# rekick2015-Prototyp-Sperrwandler.net
KiCad netlist of a schematic drawn in EAGLE
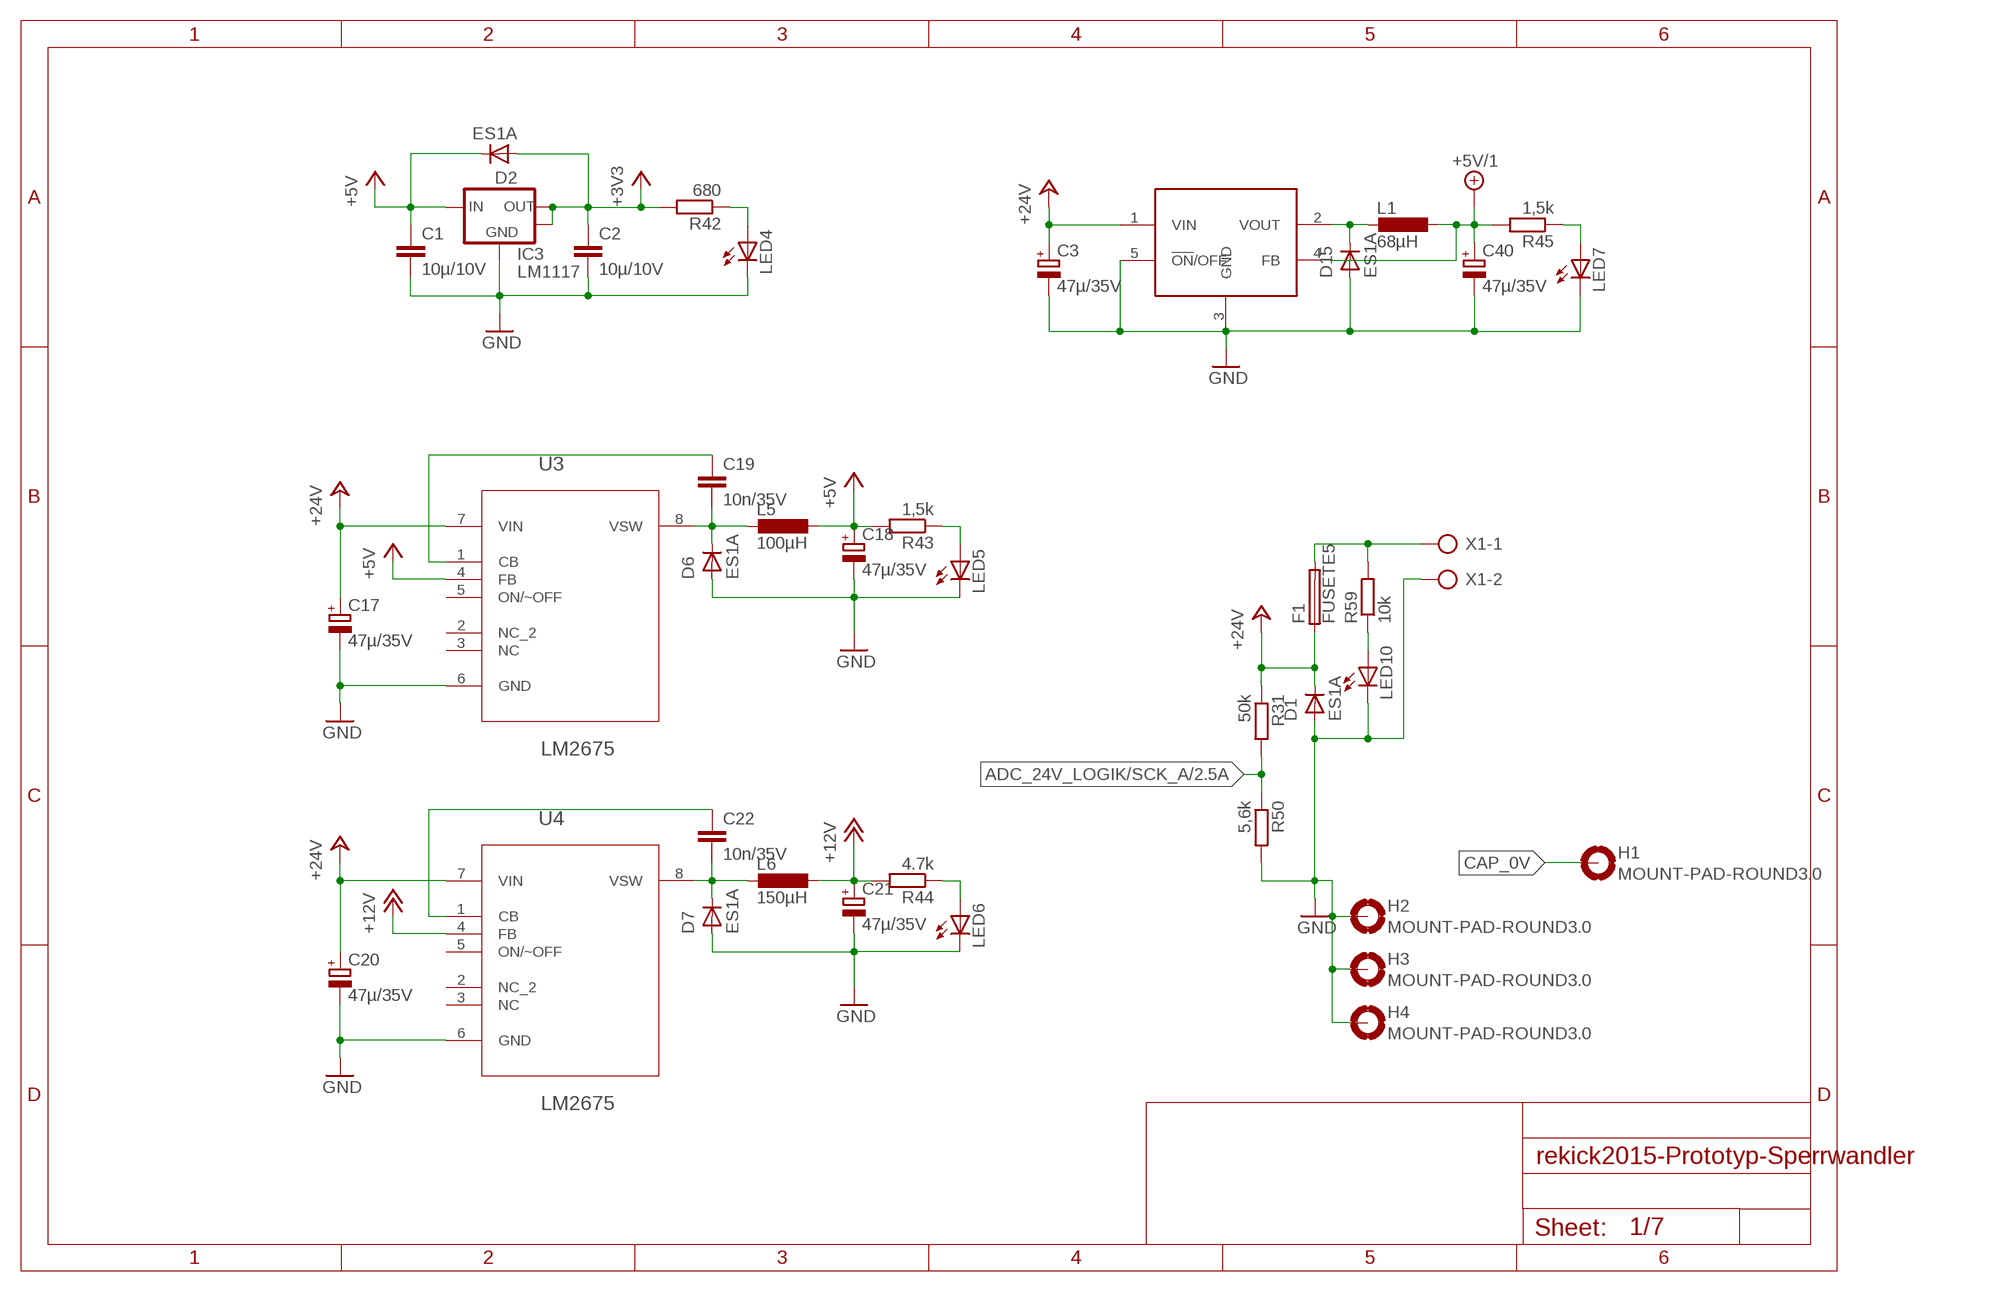
[diagram p0: schematic, sheet 1]
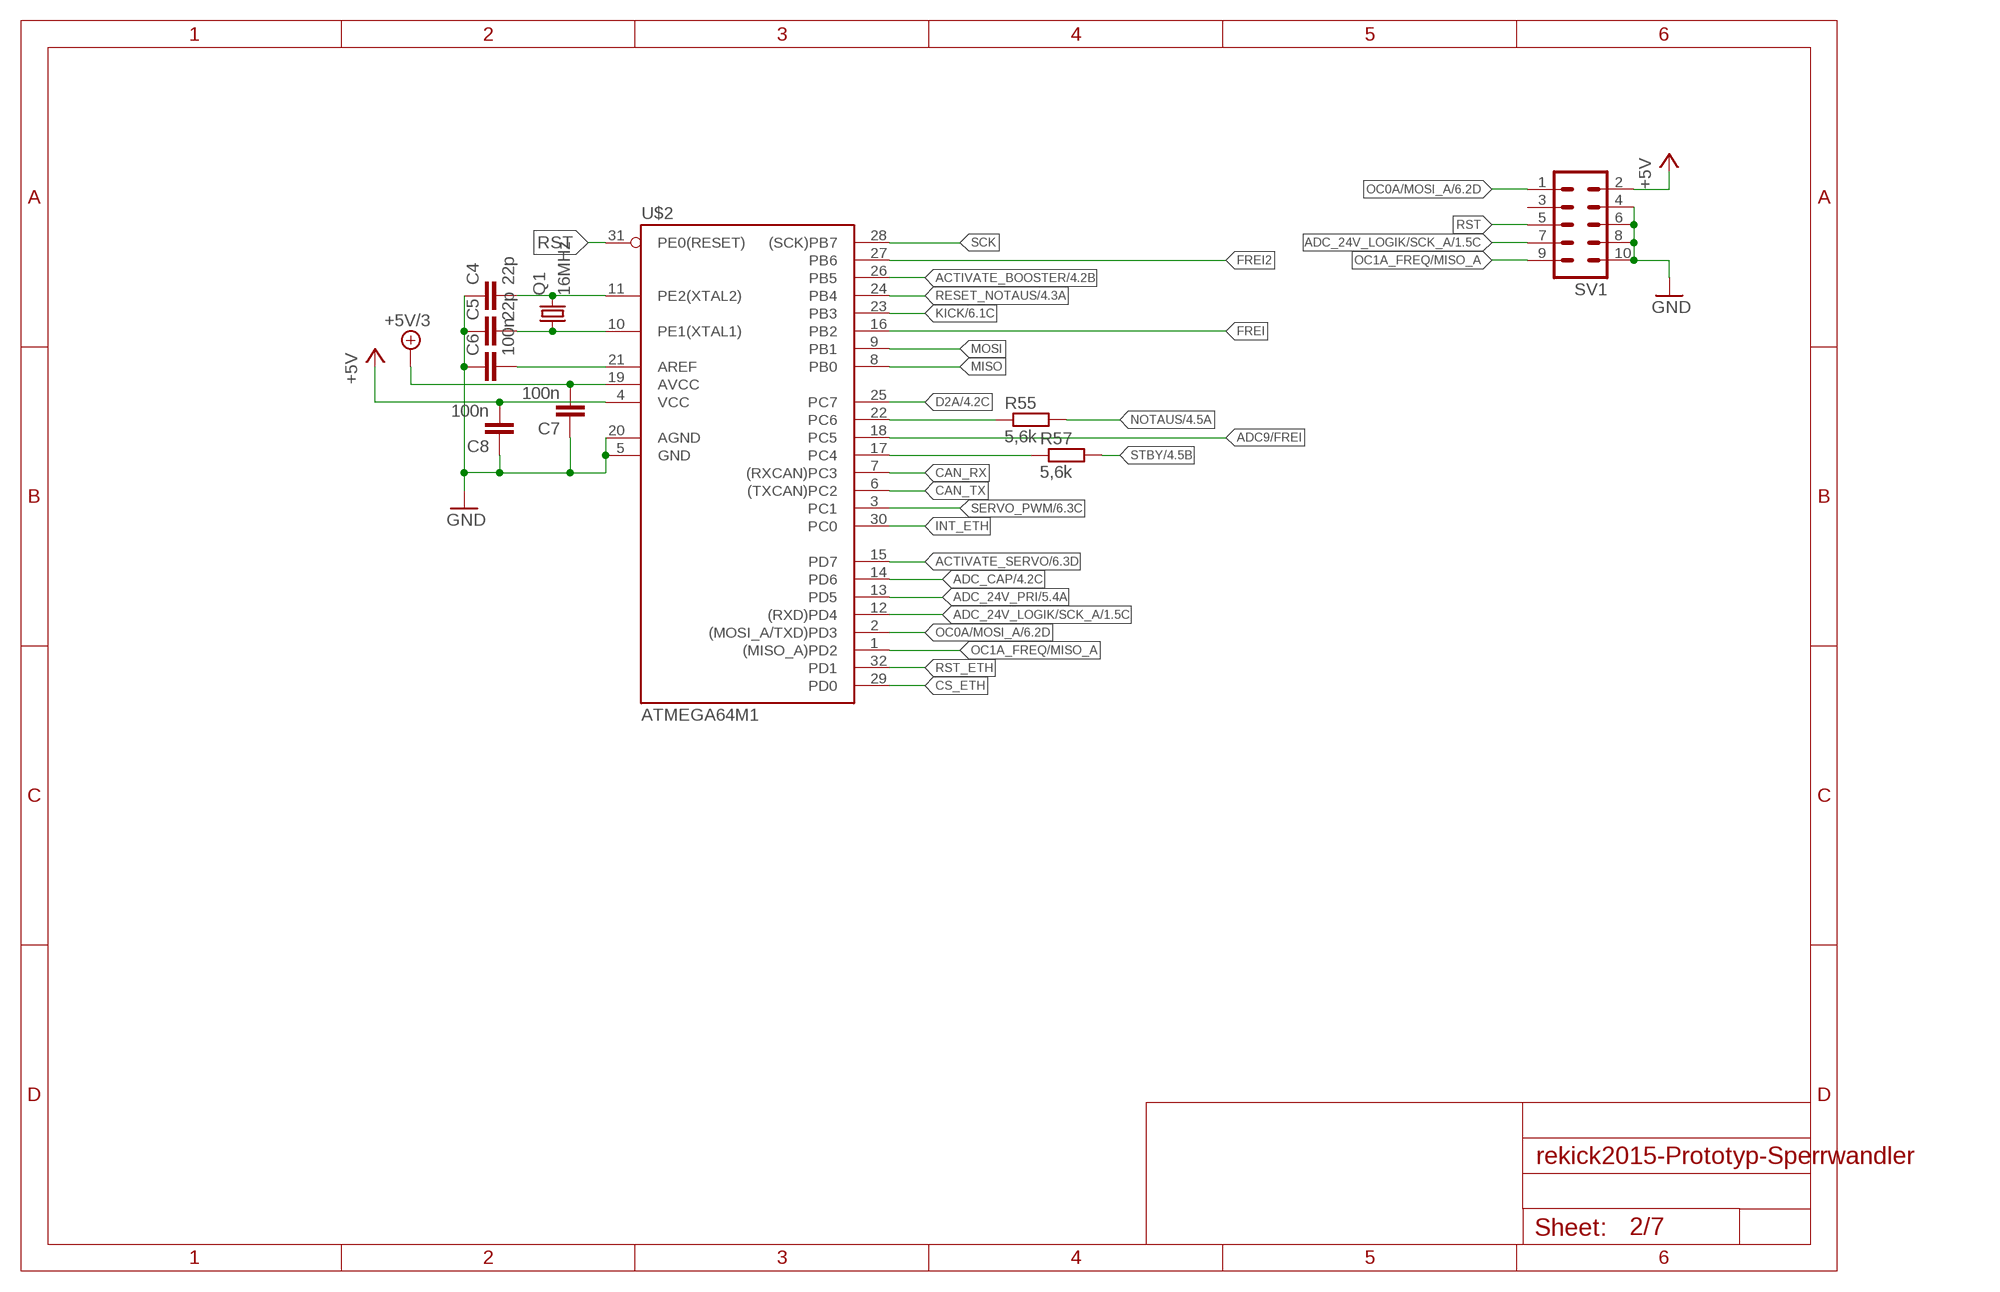
[diagram p1: schematic, sheet 2]
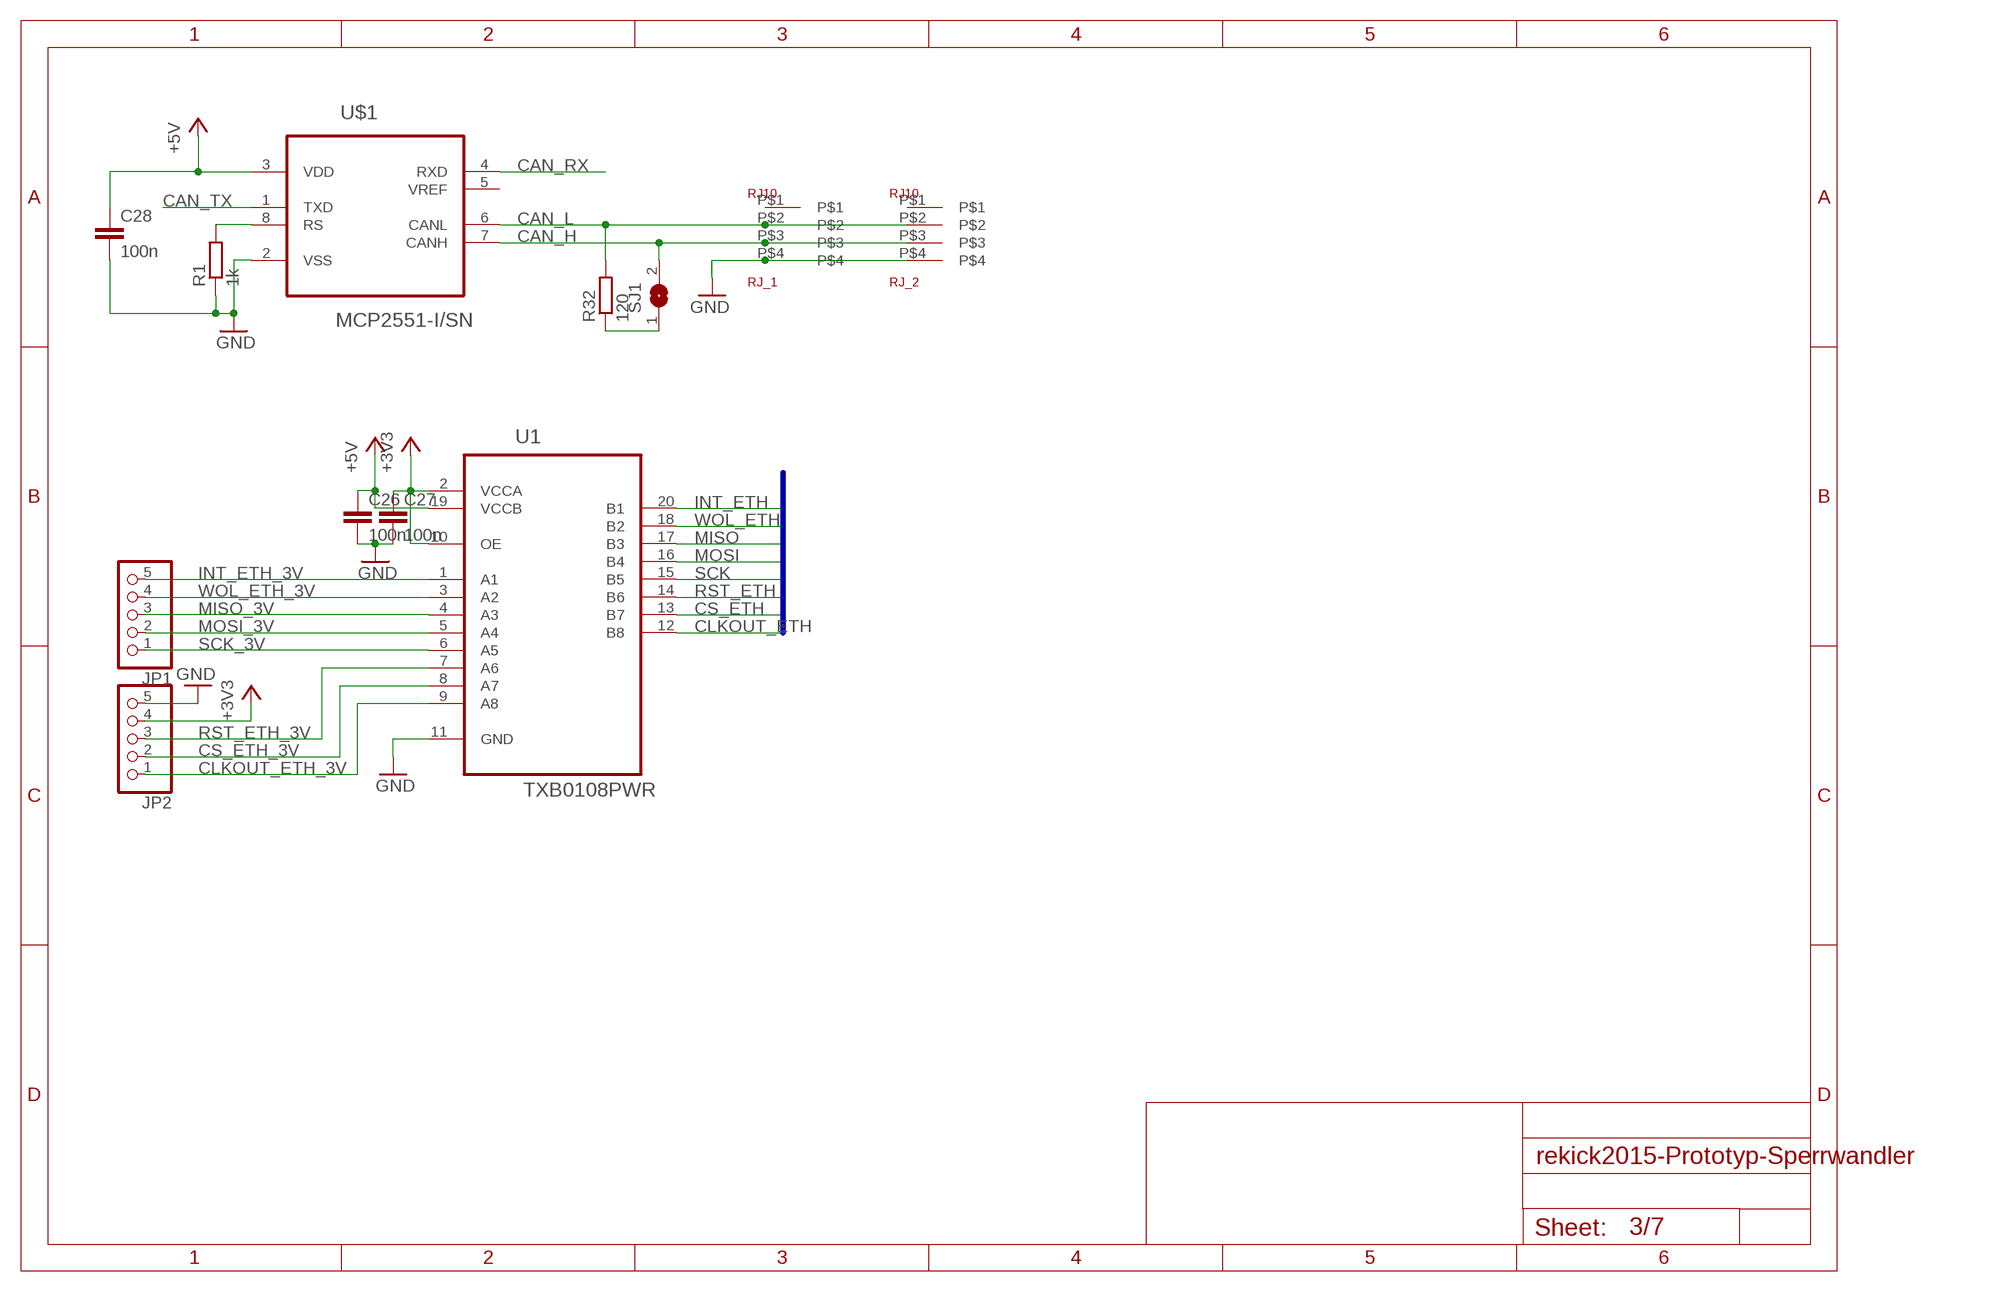
[diagram p2: schematic, sheet 3]
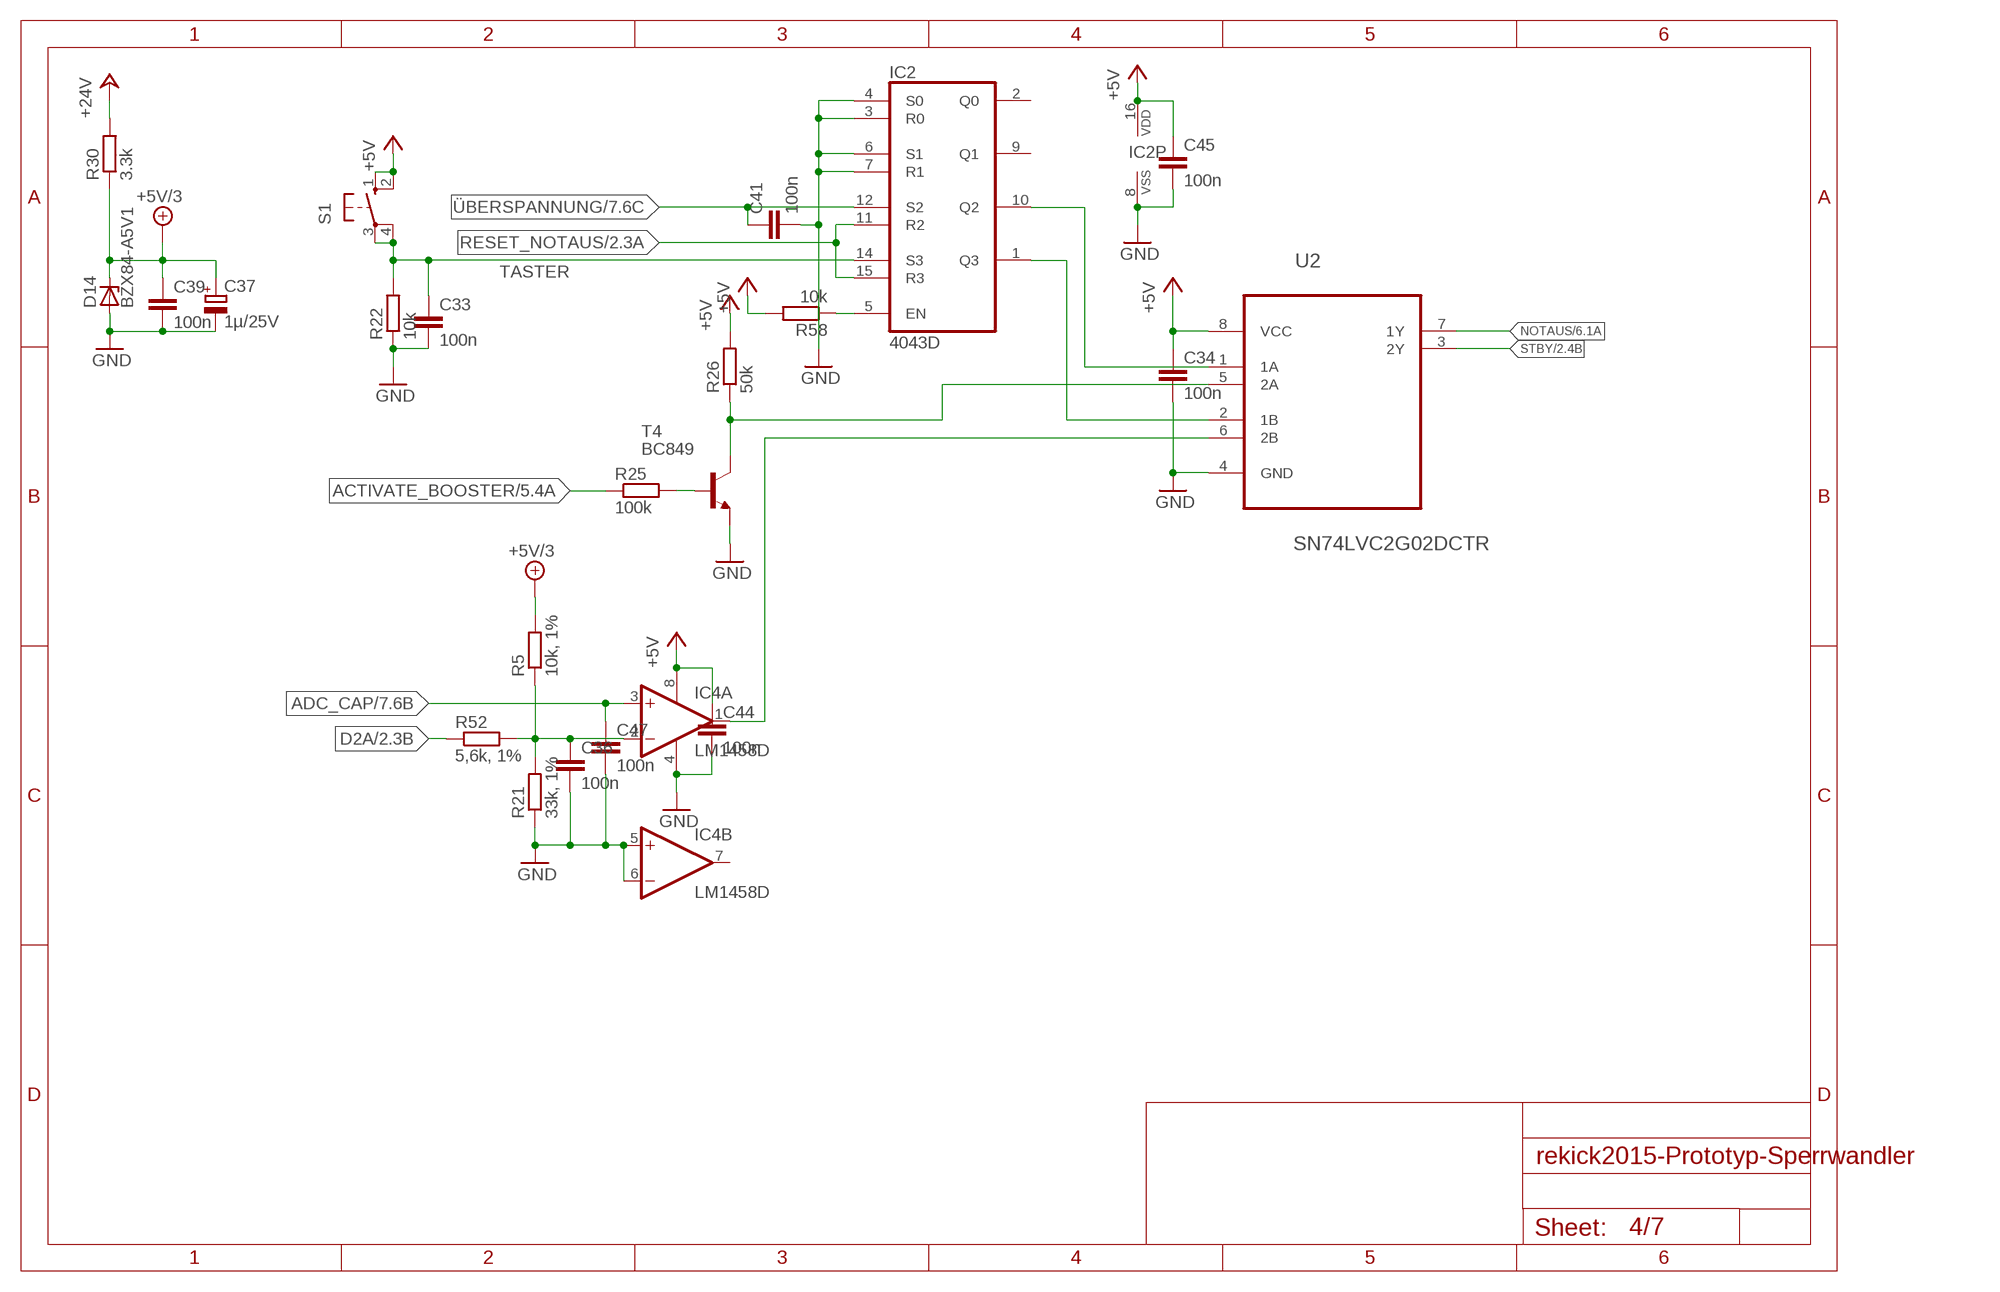
[diagram p3: schematic, sheet 4]
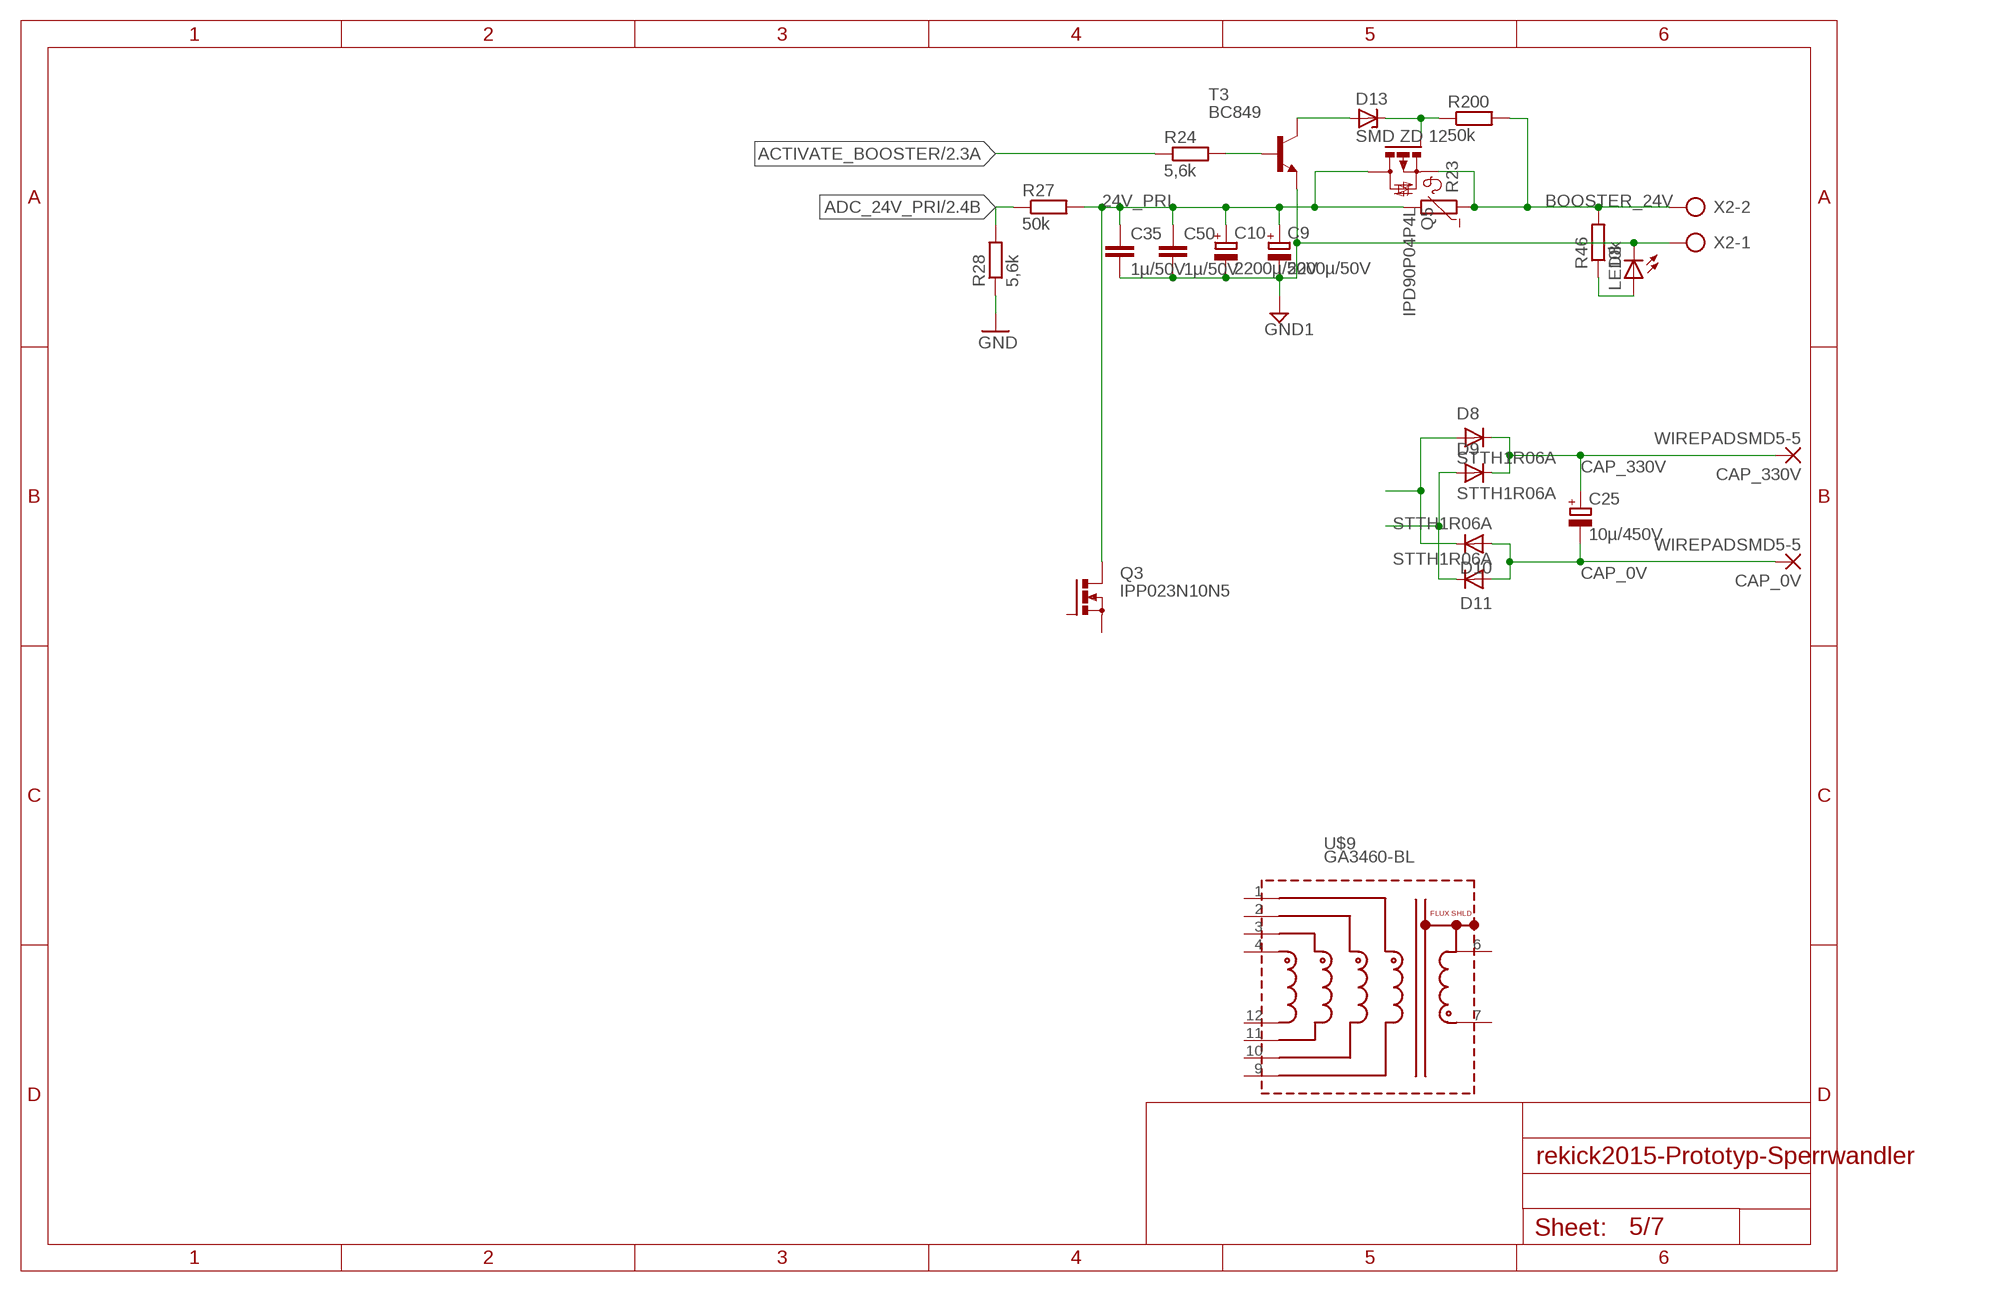
[diagram p4: schematic, sheet 5]
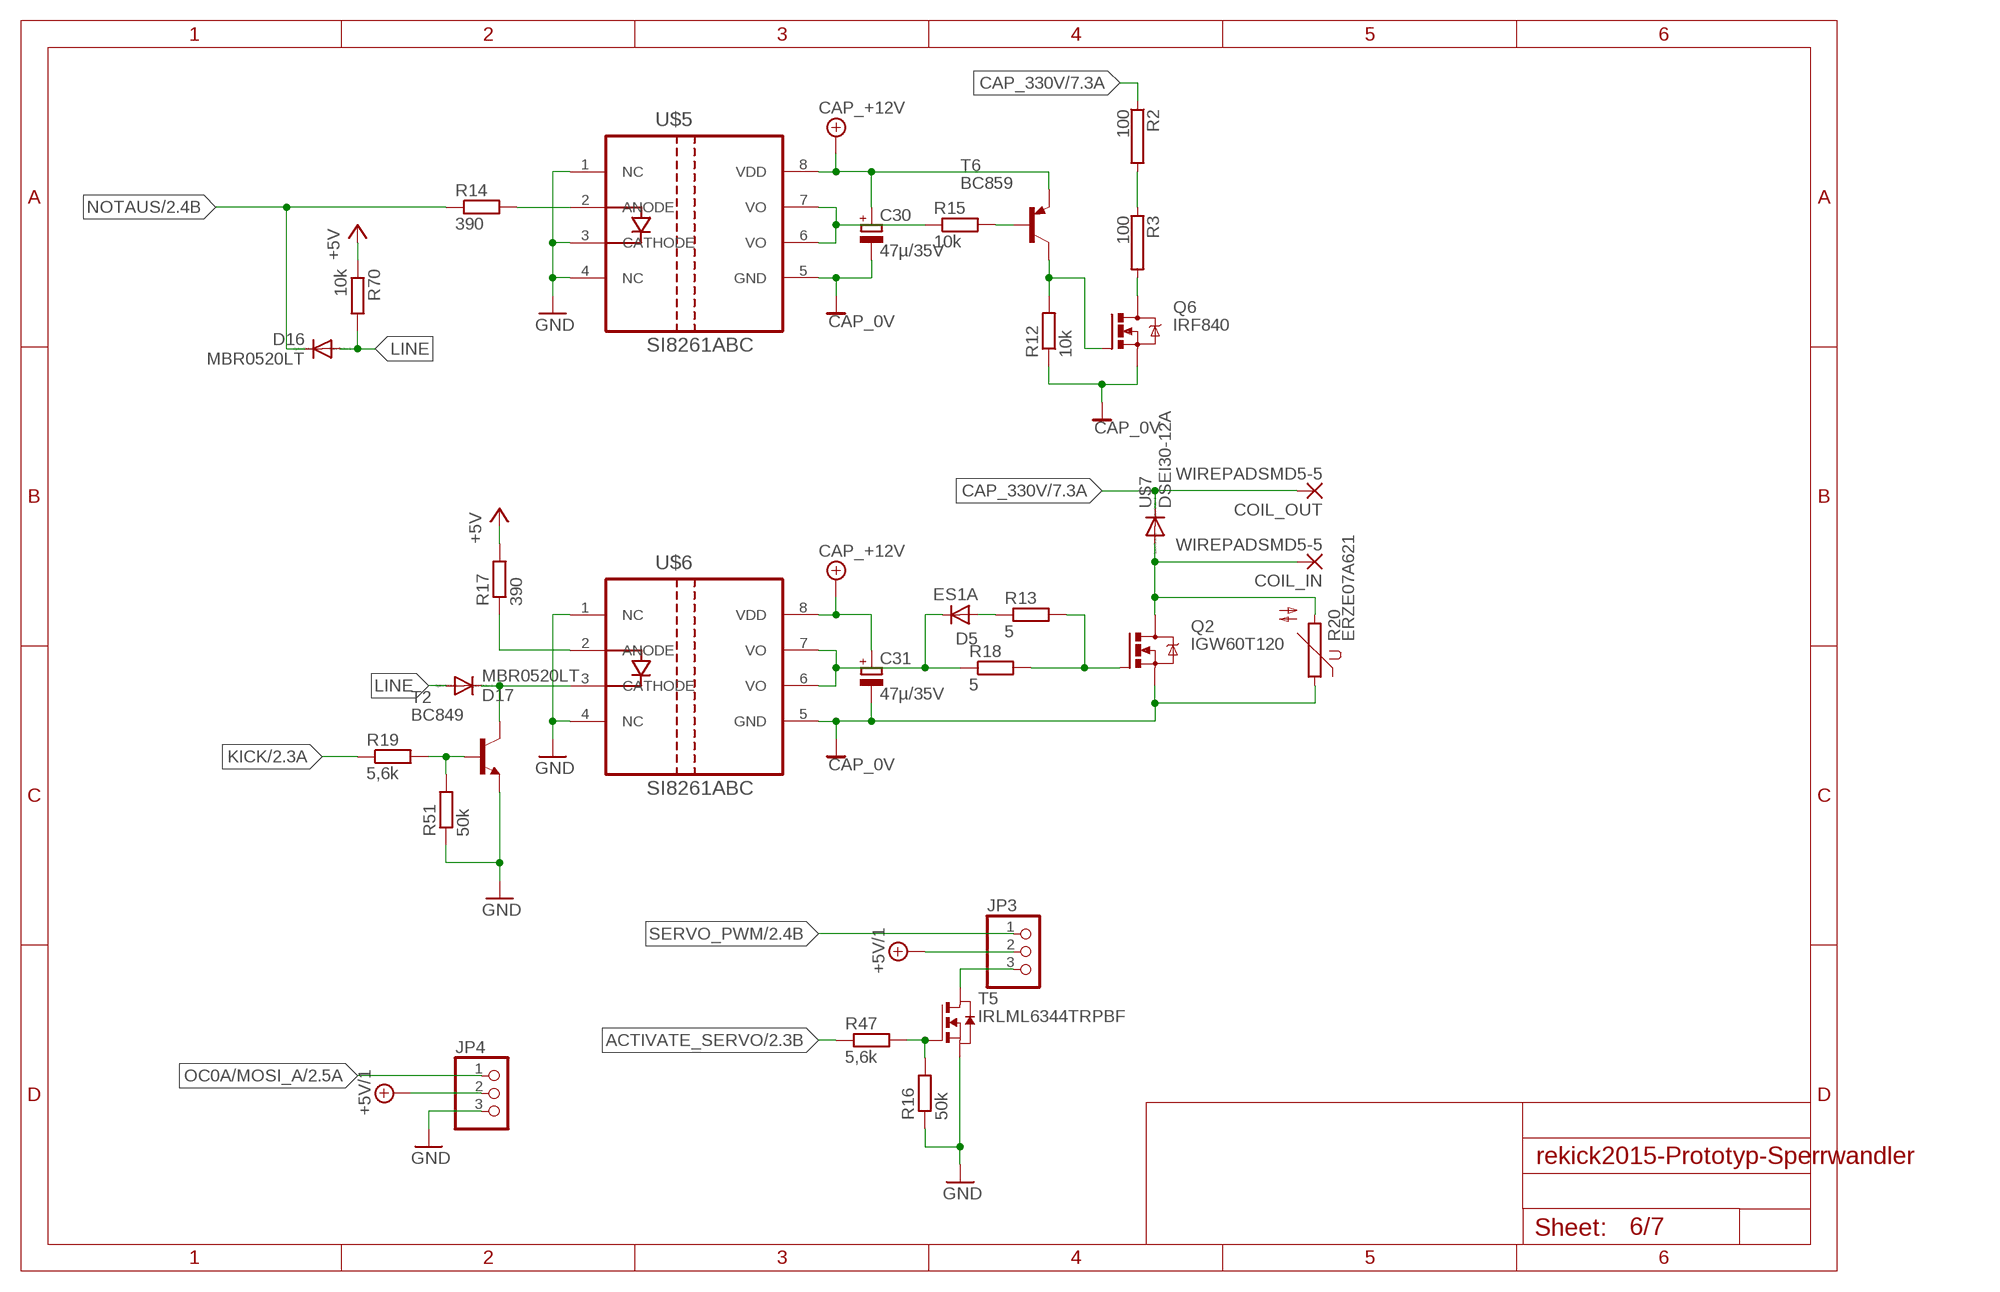
[diagram p5: schematic, sheet 6]
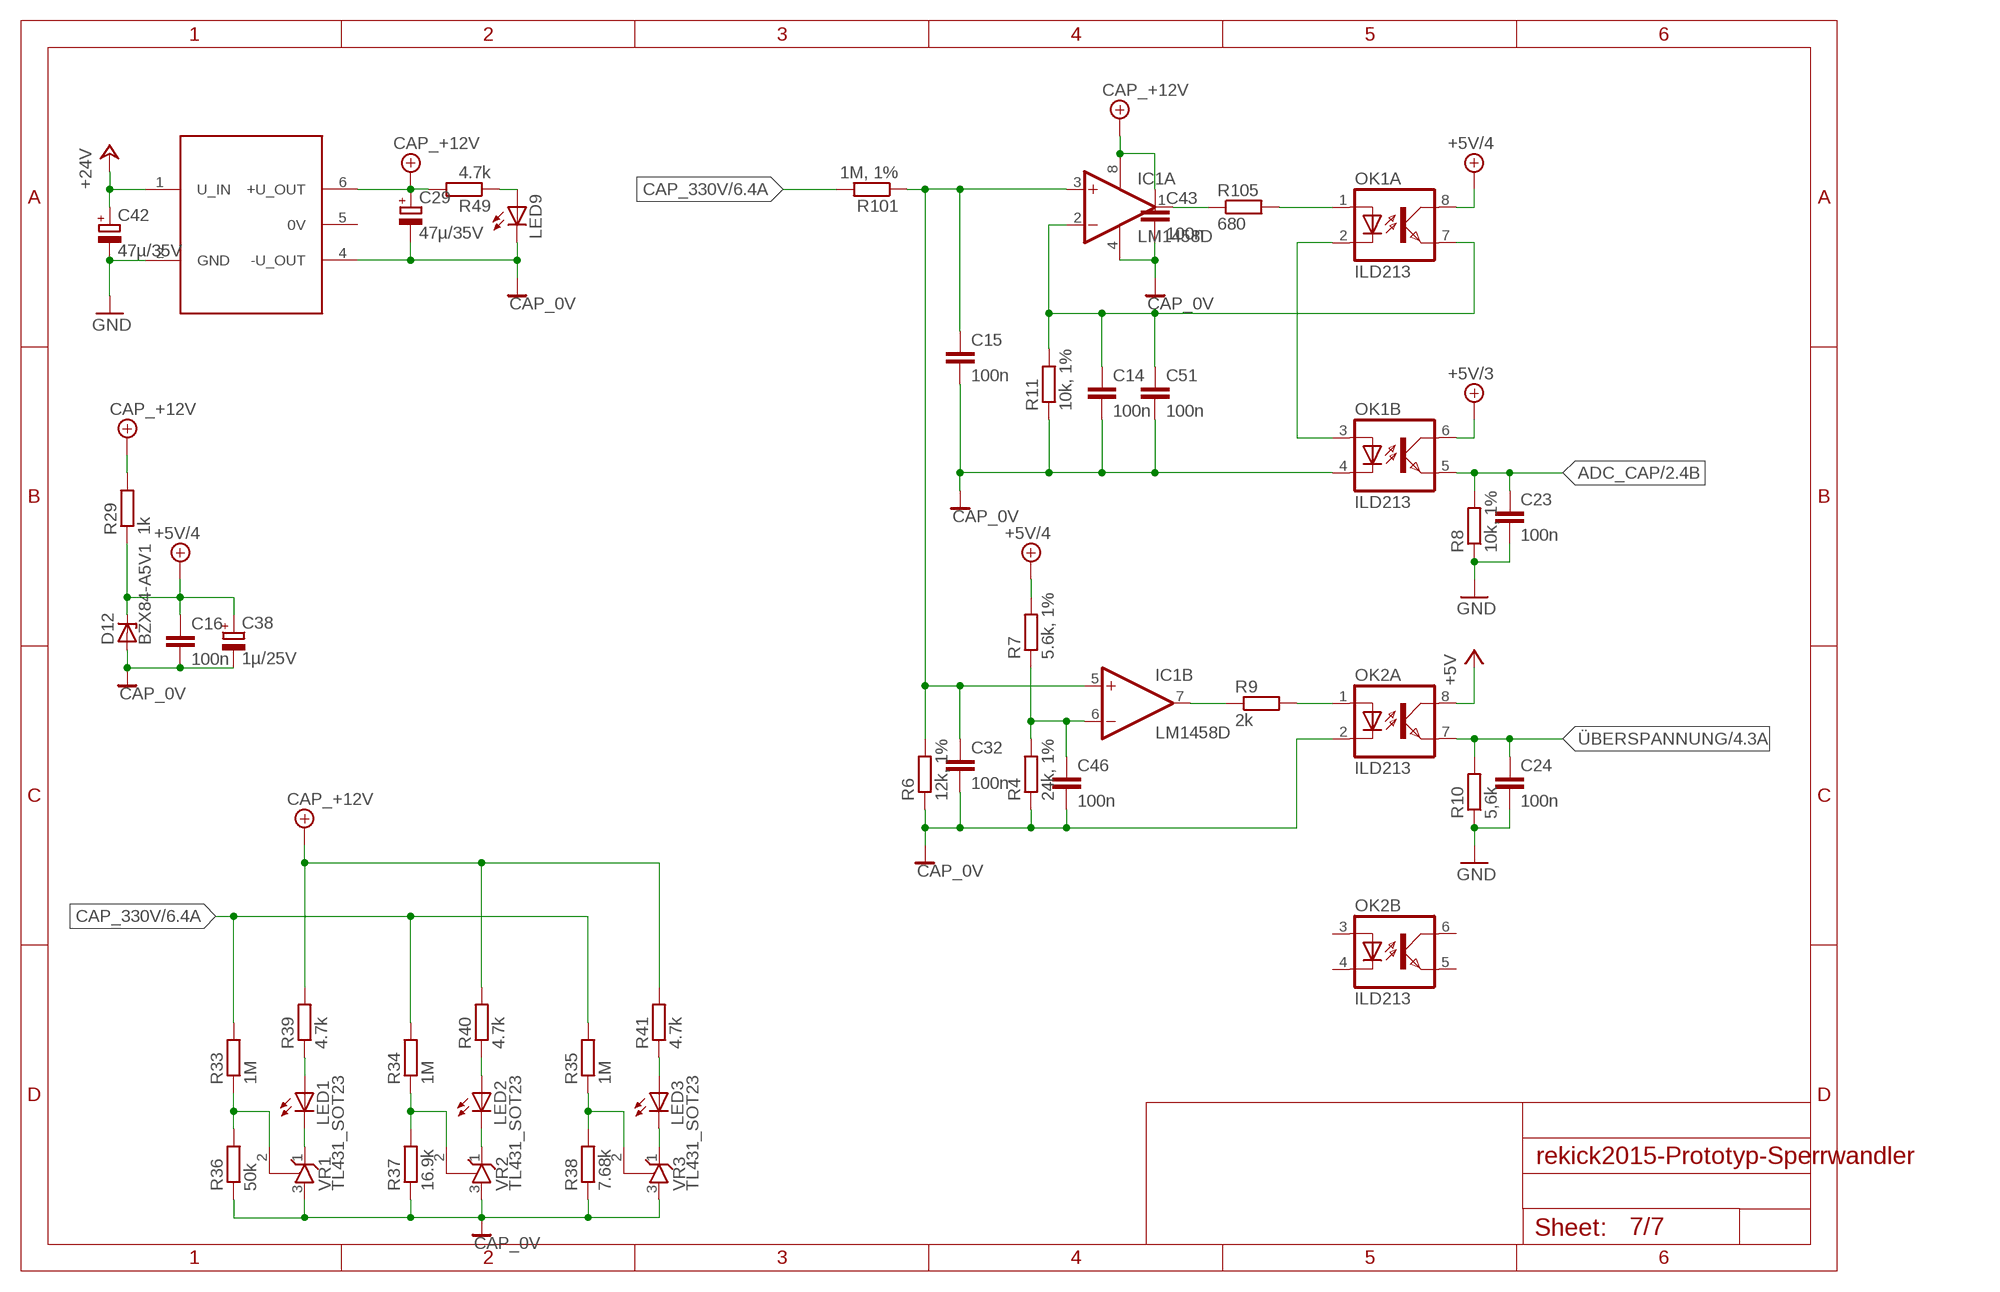
[diagram p6: schematic, sheet 7]

(export (version "E")
  (design (tool "Eeschema 10.0.6"))
  (components
    (comp (ref "C9")
      (value "2200µ/50V")
      (footprint "eagle-import:E5-13")
      (libsource (lib "eagle-import") (part "CPOL-EUE5-13"))
    )
    (comp (ref "C10")
      (value "2200µ/50V")
      (footprint "eagle-import:E5-13")
      (libsource (lib "eagle-import") (part "CPOL-EUE5-13"))
    )
    (comp (ref "C25")
      (value "10µ/450V")
      (footprint "eagle-import:E5-10,5")
      (libsource (lib "eagle-import") (part "CPOL-EUE5-10.5"))
    )
    (comp (ref "C35")
      (value "1µ/50V")
      (footprint "eagle-import:C1206")
      (libsource (lib "eagle-import") (part "C-EUC1206"))
    )
    (comp (ref "C50")
      (value "1µ/50V")
      (footprint "eagle-import:C1206")
      (libsource (lib "eagle-import") (part "C-EUC1206"))
    )
    (comp (ref "CAP_0V")
      (value "WIREPADSMD5-5")
      (footprint "eagle-import:5-5")
      (libsource (lib "eagle-import") (part "WIREPADSMD5-5"))
    )
    (comp (ref "CAP_330V")
      (value "WIREPADSMD5-5")
      (footprint "eagle-import:5-5")
      (libsource (lib "eagle-import") (part "WIREPADSMD5-5"))
    )
    (comp (ref "D8")
      (value "STTH1R06A")
      (footprint "eagle-import:SMA-DO214AC")
      (libsource (lib "eagle-import") (part "GF1"))
    )
    (comp (ref "D9")
      (value "STTH1R06A")
      (footprint "eagle-import:SMA-DO214AC")
      (libsource (lib "eagle-import") (part "GF1"))
    )
    (comp (ref "D10")
      (value "STTH1R06A")
      (footprint "eagle-import:SMA-DO214AC")
      (libsource (lib "eagle-import") (part "GF1"))
    )
    (comp (ref "D11")
      (value "STTH1R06A")
      (footprint "eagle-import:SMA-DO214AC")
      (libsource (lib "eagle-import") (part "GF1"))
    )
    (comp (ref "D13")
      (value "SMD ZD 12")
      (footprint "eagle-import:TO236")
      (libsource (lib "eagle-import") (part "BZX84CSMD"))
    )
    (comp (ref "LED8")
      (value "LEDCHIP-LED0805")
      (footprint "eagle-import:CHIP-LED0805")
      (libsource (lib "eagle-import") (part "LEDCHIP-LED0805"))
    )
    (comp (ref "Q3")
      (value "IPP023N10N5")
      (footprint "eagle-import:TO220BV")
      (libsource (lib "eagle-import") (part "PMOSFET_NTO220BV"))
    )
    (comp (ref "Q5")
      (value "IPD90P04P4L")
      (footprint "eagle-import:D-PAK_TO252AA")
      (libsource (lib "eagle-import") (part "IRF?5305R"))
    )
    (comp (ref "R23")
      (value "NTC644A")
      (footprint "eagle-import:N644A")
      (libsource (lib "eagle-import") (part "NTC644A"))
    )
    (comp (ref "R24")
      (value "5,6k")
      (footprint "eagle-import:R0805")
      (libsource (lib "eagle-import") (part "R-EU_R0805"))
    )
    (comp (ref "R27")
      (value "50k")
      (footprint "eagle-import:R0805")
      (libsource (lib "eagle-import") (part "R-EU_R0805"))
    )
    (comp (ref "R28")
      (value "5,6k")
      (footprint "eagle-import:R0805")
      (libsource (lib "eagle-import") (part "R-EU_R0805"))
    )
    (comp (ref "R46")
      (value "10k")
      (footprint "eagle-import:R0805")
      (libsource (lib "eagle-import") (part "R-EU_R0805"))
    )
    (comp (ref "R200")
      (value "50k")
      (footprint "eagle-import:R0805")
      (libsource (lib "eagle-import") (part "R-EU_R0805"))
    )
    (comp (ref "T3")
      (value "BC849")
      (footprint "eagle-import:SOT23")
      (libsource (lib "eagle-import") (part "BC849"))
    )
    (comp (ref "U$9")
      (value "GA3460-BL")
      (footprint "eagle-import:GA3459")
      (libsource (lib "eagle-import") (part "GA3460-BL"))
    )
    (comp (ref "X2")
      (value "AK500/2-H")
      (footprint "eagle-import:AK500_2-H")
      (libsource (lib "eagle-import") (part "AK500/2-H"))
    )
    (comp (ref "C30")
      (value "47µ/35V")
      (footprint "eagle-import:E2-5")
      (libsource (lib "eagle-import") (part "CPOL-EUE2-5"))
    )
    (comp (ref "C31")
      (value "47µ/35V")
      (footprint "eagle-import:E2-5")
      (libsource (lib "eagle-import") (part "CPOL-EUE2-5"))
    )
    (comp (ref "COIL_IN")
      (value "WIREPADSMD5-5")
      (footprint "eagle-import:5-5")
      (libsource (lib "eagle-import") (part "WIREPADSMD5-5"))
    )
    (comp (ref "COIL_OUT")
      (value "WIREPADSMD5-5")
      (footprint "eagle-import:5-5")
      (libsource (lib "eagle-import") (part "WIREPADSMD5-5"))
    )
    (comp (ref "D5")
      (value "ES1A")
      (footprint "eagle-import:SMA-DO214AC")
      (libsource (lib "eagle-import") (part "GF1"))
    )
    (comp (ref "D16")
      (value "MBR0520LT")
      (footprint "eagle-import:SOD123")
      (libsource (lib "eagle-import") (part "MBR0520LT"))
    )
    (comp (ref "D17")
      (value "MBR0520LT")
      (footprint "eagle-import:SOD123")
      (libsource (lib "eagle-import") (part "MBR0520LT"))
    )
    (comp (ref "JP3")
      (value "PINHD-1X3")
      (footprint "eagle-import:1X03")
      (libsource (lib "eagle-import") (part "PINHD-1X3"))
    )
    (comp (ref "JP4")
      (value "PINHD-1X3")
      (footprint "eagle-import:1X03")
      (libsource (lib "eagle-import") (part "PINHD-1X3"))
    )
    (comp (ref "Q2")
      (value "IGW60T120")
      (footprint "eagle-import:TO247BV")
      (libsource (lib "eagle-import") (part "IRFPC40"))
    )
    (comp (ref "Q6")
      (value "IRF840")
      (footprint "eagle-import:TO220BV")
      (libsource (lib "eagle-import") (part "IRF740"))
    )
    (comp (ref "R2")
      (value "100")
      (footprint "eagle-import:HS25")
      (libsource (lib "eagle-import") (part "RHS25"))
    )
    (comp (ref "R3")
      (value "100")
      (footprint "eagle-import:HS25")
      (libsource (lib "eagle-import") (part "RHS25"))
    )
    (comp (ref "R12")
      (value "10k")
      (footprint "eagle-import:R0805")
      (libsource (lib "eagle-import") (part "R-EU_R0805"))
    )
    (comp (ref "R13")
      (value "5")
      (footprint "eagle-import:R2512")
      (libsource (lib "eagle-import") (part "R-EU_R2512"))
    )
    (comp (ref "R14")
      (value "390")
      (footprint "eagle-import:R0805")
      (libsource (lib "eagle-import") (part "R-EU_R0805"))
    )
    (comp (ref "R15")
      (value "10k")
      (footprint "eagle-import:R0805")
      (libsource (lib "eagle-import") (part "R-EU_R0805"))
    )
    (comp (ref "R16")
      (value "50k")
      (footprint "eagle-import:R0805")
      (libsource (lib "eagle-import") (part "R-EU_R0805"))
    )
    (comp (ref "R17")
      (value "390")
      (footprint "eagle-import:R0805")
      (libsource (lib "eagle-import") (part "R-EU_R0805"))
    )
    (comp (ref "R18")
      (value "5")
      (footprint "eagle-import:R2512")
      (libsource (lib "eagle-import") (part "R-EU_R2512"))
    )
    (comp (ref "R19")
      (value "5,6k")
      (footprint "eagle-import:R0805")
      (libsource (lib "eagle-import") (part "R-EU_R0805"))
    )
    (comp (ref "R20")
      (value "ERZE07A621")
      (footprint "eagle-import:S10K385")
      (libsource (lib "eagle-import") (part "S10K385"))
    )
    (comp (ref "R47")
      (value "5,6k")
      (footprint "eagle-import:R0805")
      (libsource (lib "eagle-import") (part "R-EU_R0805"))
    )
    (comp (ref "R51")
      (value "50k")
      (footprint "eagle-import:R0805")
      (libsource (lib "eagle-import") (part "R-EU_R0805"))
    )
    (comp (ref "R70")
      (value "10k")
      (footprint "eagle-import:R0805")
      (libsource (lib "eagle-import") (part "R-EU_R0805"))
    )
    (comp (ref "T2")
      (value "BC849")
      (footprint "eagle-import:SOT23")
      (libsource (lib "eagle-import") (part "BC849"))
    )
    (comp (ref "T5")
      (value "IRLML6344TRPBF")
      (footprint "eagle-import:SOT-23")
      (libsource (lib "eagle-import") (part "NMOSSOT23"))
    )
    (comp (ref "T6")
      (value "BC859")
      (footprint "eagle-import:SOT23-BEC")
      (libsource (lib "eagle-import") (part "-PNP-SOT23-BECBC858C"))
    )
    (comp (ref "U$5")
      (value "SI8261ABC")
      (footprint "eagle-import:SOIC-8")
      (libsource (lib "eagle-import") (part "SI8261ABC"))
    )
    (comp (ref "U$6")
      (value "SI8261ABC")
      (footprint "eagle-import:SOIC-8")
      (libsource (lib "eagle-import") (part "SI8261ABC"))
    )
    (comp (ref "U$7")
      (value "DSEI30-12A")
      (footprint "eagle-import:TO247AD")
      (libsource (lib "eagle-import") (part "DSEI30-12A"))
    )
    (comp (ref "C26")
      (value "100n")
      (footprint "eagle-import:C0603")
      (libsource (lib "eagle-import") (part "C-EUC0603"))
    )
    (comp (ref "C27")
      (value "100n")
      (footprint "eagle-import:C0603")
      (libsource (lib "eagle-import") (part "C-EUC0603"))
    )
    (comp (ref "C28")
      (value "100n")
      (footprint "eagle-import:C0603")
      (libsource (lib "eagle-import") (part "C-EUC0603"))
    )
    (comp (ref "JP1")
      (value "PINHD-1X5")
      (footprint "eagle-import:1X05")
      (libsource (lib "eagle-import") (part "PINHD-1X5"))
    )
    (comp (ref "JP2")
      (value "PINHD-1X5")
      (footprint "eagle-import:1X05")
      (libsource (lib "eagle-import") (part "PINHD-1X5"))
    )
    (comp (ref "R1")
      (value "1k")
      (footprint "eagle-import:R0805")
      (libsource (lib "eagle-import") (part "R-EU_R0805"))
    )
    (comp (ref "R32")
      (value "120")
      (footprint "eagle-import:R0805")
      (libsource (lib "eagle-import") (part "R-EU_R0805"))
    )
    (comp (ref "RJ_1")
      (value "RJ10")
      (footprint "eagle-import:RJ10")
      (libsource (lib "eagle-import") (part "RJ10"))
    )
    (comp (ref "RJ_2")
      (value "RJ10")
      (footprint "eagle-import:RJ10")
      (libsource (lib "eagle-import") (part "RJ10"))
    )
    (comp (ref "SJ1") (value "SJ") (footprint "eagle-import:SJ") (libsource (lib "eagle-import") (part "SJ")))
    (comp (ref "U$1")
      (value "MCP2551-I/SN")
      (footprint "eagle-import:SOIC127P600X175-8N")
      (libsource (lib "eagle-import") (part "MCP2551-I/SN"))
    )
    (comp (ref "U1")
      (value "TXB0108PWR")
      (footprint "eagle-import:SOP65P640X120-20N")
      (libsource (lib "eagle-import") (part "TXB0108PWR"))
    )
    (comp (ref "C1")
      (value "10µ/10V")
      (footprint "eagle-import:C0603")
      (libsource (lib "eagle-import") (part "C-EUC0603"))
    )
    (comp (ref "C2")
      (value "10µ/10V")
      (footprint "eagle-import:C0603")
      (libsource (lib "eagle-import") (part "C-EUC0603"))
    )
    (comp (ref "C3")
      (value "47µ/35V")
      (footprint "eagle-import:PANASONIC_D")
      (libsource (lib "eagle-import") (part "CPOL-EUD"))
    )
    (comp (ref "C17")
      (value "47µ/35V")
      (footprint "eagle-import:PANASONIC_D")
      (libsource (lib "eagle-import") (part "CPOL-EUD"))
    )
    (comp (ref "C18")
      (value "47µ/35V")
      (footprint "eagle-import:PANASONIC_D")
      (libsource (lib "eagle-import") (part "CPOL-EUD"))
    )
    (comp (ref "C19")
      (value "10n/35V")
      (footprint "eagle-import:C0603")
      (libsource (lib "eagle-import") (part "C-EUC0603"))
    )
    (comp (ref "C20")
      (value "47µ/35V")
      (footprint "eagle-import:PANASONIC_D")
      (libsource (lib "eagle-import") (part "CPOL-EUD"))
    )
    (comp (ref "C21")
      (value "47µ/35V")
      (footprint "eagle-import:PANASONIC_D")
      (libsource (lib "eagle-import") (part "CPOL-EUD"))
    )
    (comp (ref "C22")
      (value "10n/35V")
      (footprint "eagle-import:C0603")
      (libsource (lib "eagle-import") (part "C-EUC0603"))
    )
    (comp (ref "C40")
      (value "47µ/35V")
      (footprint "eagle-import:PANASONIC_D")
      (libsource (lib "eagle-import") (part "CPOL-EUD"))
    )
    (comp (ref "D1")
      (value "ES1A")
      (footprint "eagle-import:SMA-DO214AC")
      (libsource (lib "eagle-import") (part "GF1"))
    )
    (comp (ref "D2")
      (value "ES1A")
      (footprint "eagle-import:SMA-DO214AC")
      (libsource (lib "eagle-import") (part "GF1"))
    )
    (comp (ref "D6")
      (value "ES1A")
      (footprint "eagle-import:SMA-DO214AC")
      (libsource (lib "eagle-import") (part "GF1"))
    )
    (comp (ref "D7")
      (value "ES1A")
      (footprint "eagle-import:SMA-DO214AC")
      (libsource (lib "eagle-import") (part "GF1"))
    )
    (comp (ref "D15")
      (value "ES1A")
      (footprint "eagle-import:SMA-DO214AC")
      (libsource (lib "eagle-import") (part "GF1"))
    )
    (comp (ref "F1")
      (value "FUSETE5")
      (footprint "eagle-import:TE5")
      (libsource (lib "eagle-import") (part "FUSETE5"))
    )
    (comp (ref "H1")
      (value "MOUNT-PAD-ROUND3.0")
      (footprint "eagle-import:3,0-PAD")
      (libsource (lib "eagle-import") (part "MOUNT-PAD-ROUND3.0"))
    )
    (comp (ref "H2")
      (value "MOUNT-PAD-ROUND3.0")
      (footprint "eagle-import:3,0-PAD")
      (libsource (lib "eagle-import") (part "MOUNT-PAD-ROUND3.0"))
    )
    (comp (ref "H3")
      (value "MOUNT-PAD-ROUND3.0")
      (footprint "eagle-import:3,0-PAD")
      (libsource (lib "eagle-import") (part "MOUNT-PAD-ROUND3.0"))
    )
    (comp (ref "H4")
      (value "MOUNT-PAD-ROUND3.0")
      (footprint "eagle-import:3,0-PAD")
      (libsource (lib "eagle-import") (part "MOUNT-PAD-ROUND3.0"))
    )
    (comp (ref "IC3")
      (value "LM1117")
      (footprint "eagle-import:SOT223")
      (libsource (lib "eagle-import") (part "LM1117"))
    )
    (comp (ref "L1")
      (value "68µH")
      (footprint "eagle-import:PISM")
      (libsource (lib "eagle-import") (part "L-EUPISM"))
    )
    (comp (ref "L5")
      (value "100µH")
      (footprint "eagle-import:PISM")
      (libsource (lib "eagle-import") (part "L-EUPISM"))
    )
    (comp (ref "L6")
      (value "150µH")
      (footprint "eagle-import:PISM")
      (libsource (lib "eagle-import") (part "L-EUPISM"))
    )
    (comp (ref "LED4")
      (value "LEDCHIP-LED0805")
      (footprint "eagle-import:CHIP-LED0805")
      (libsource (lib "eagle-import") (part "LEDCHIP-LED0805"))
    )
    (comp (ref "LED5")
      (value "LEDCHIP-LED0805")
      (footprint "eagle-import:CHIP-LED0805")
      (libsource (lib "eagle-import") (part "LEDCHIP-LED0805"))
    )
    (comp (ref "LED6")
      (value "LEDCHIP-LED0805")
      (footprint "eagle-import:CHIP-LED0805")
      (libsource (lib "eagle-import") (part "LEDCHIP-LED0805"))
    )
    (comp (ref "LED7")
      (value "LEDCHIP-LED0805")
      (footprint "eagle-import:CHIP-LED0805")
      (libsource (lib "eagle-import") (part "LEDCHIP-LED0805"))
    )
    (comp (ref "LED10")
      (value "LEDCHIP-LED0805")
      (footprint "eagle-import:CHIP-LED0805")
      (libsource (lib "eagle-import") (part "LEDCHIP-LED0805"))
    )
    (comp (ref "R31")
      (value "50k")
      (footprint "eagle-import:R0805")
      (libsource (lib "eagle-import") (part "R-EU_R0805"))
    )
    (comp (ref "R42")
      (value "680")
      (footprint "eagle-import:R0805")
      (libsource (lib "eagle-import") (part "R-EU_R0805"))
    )
    (comp (ref "R43")
      (value "1,5k")
      (footprint "eagle-import:R0805")
      (libsource (lib "eagle-import") (part "R-EU_R0805"))
    )
    (comp (ref "R44")
      (value "4.7k")
      (footprint "eagle-import:R0805")
      (libsource (lib "eagle-import") (part "R-EU_R0805"))
    )
    (comp (ref "R45")
      (value "1,5k")
      (footprint "eagle-import:R0805")
      (libsource (lib "eagle-import") (part "R-EU_R0805"))
    )
    (comp (ref "R50")
      (value "5,6k")
      (footprint "eagle-import:R0805")
      (libsource (lib "eagle-import") (part "R-EU_R0805"))
    )
    (comp (ref "R59")
      (value "10k")
      (footprint "eagle-import:R0805")
      (libsource (lib "eagle-import") (part "R-EU_R0805"))
    )
    (comp (ref "U$8")
      (value "LM2576")
      (footprint "eagle-import:TO220511")
      (libsource (lib "eagle-import") (part "LM2576"))
    )
    (comp (ref "U3")
      (value "LM2675")
      (footprint "eagle-import:SOIC127P620X175-8N")
      (fields (field (name "MPN") "LM2675M-3.3"))
      (libsource (lib "eagle-import") (part "LM2675M-3.3"))
    )
    (comp (ref "U4")
      (value "LM2675")
      (footprint "eagle-import:SOIC127P620X175-8N")
      (fields (field (name "MPN") "LM2675M-3.3"))
      (libsource (lib "eagle-import") (part "LM2675M-3.3"))
    )
    (comp (ref "X1")
      (value "AK500/2-H")
      (footprint "eagle-import:AK500_2-H")
      (libsource (lib "eagle-import") (part "AK500/2-H"))
    )
    (comp (ref "C4")
      (value "22p")
      (footprint "eagle-import:C0603")
      (libsource (lib "eagle-import") (part "C-EUC0603"))
    )
    (comp (ref "C5")
      (value "22p")
      (footprint "eagle-import:C0603")
      (libsource (lib "eagle-import") (part "C-EUC0603"))
    )
    (comp (ref "C6")
      (value "100n")
      (footprint "eagle-import:C0603")
      (libsource (lib "eagle-import") (part "C-EUC0603"))
    )
    (comp (ref "C7")
      (value "100n")
      (footprint "eagle-import:C0603")
      (libsource (lib "eagle-import") (part "C-EUC0603"))
    )
    (comp (ref "C8")
      (value "100n")
      (footprint "eagle-import:C0603")
      (libsource (lib "eagle-import") (part "C-EUC0603"))
    )
    (comp (ref "Q1")
      (value "16MHz")
      (footprint "eagle-import:HC49UP")
      (libsource (lib "eagle-import") (part "CRYSTALHC49UP"))
    )
    (comp (ref "R55")
      (value "5,6k")
      (footprint "eagle-import:R0805")
      (libsource (lib "eagle-import") (part "R-EU_R0805"))
    )
    (comp (ref "R57")
      (value "5,6k")
      (footprint "eagle-import:R0805")
      (libsource (lib "eagle-import") (part "R-EU_R0805"))
    )
    (comp (ref "SV1")
      (value "ML10")
      (footprint "eagle-import:ML10")
      (libsource (lib "eagle-import") (part "ML10"))
    )
    (comp (ref "U$2")
      (value "ATMEGA64M1")
      (footprint "eagle-import:TQFP32-08")
      (libsource (lib "eagle-import") (part "ATMEGA64M1"))
    )
    (comp (ref "C14")
      (value "100n")
      (footprint "eagle-import:C0603")
      (libsource (lib "eagle-import") (part "C-EUC0603"))
    )
    (comp (ref "C15")
      (value "100n")
      (footprint "eagle-import:C0603")
      (libsource (lib "eagle-import") (part "C-EUC0603"))
    )
    (comp (ref "C16")
      (value "100n")
      (footprint "eagle-import:C0603")
      (libsource (lib "eagle-import") (part "C-EUC0603"))
    )
    (comp (ref "C23")
      (value "100n")
      (footprint "eagle-import:C0603")
      (libsource (lib "eagle-import") (part "C-EUC0603"))
    )
    (comp (ref "C24")
      (value "100n")
      (footprint "eagle-import:C0603")
      (libsource (lib "eagle-import") (part "C-EUC0603"))
    )
    (comp (ref "C29")
      (value "47µ/35V")
      (footprint "eagle-import:PANASONIC_D")
      (libsource (lib "eagle-import") (part "CPOL-EUD"))
    )
    (comp (ref "C32")
      (value "100n")
      (footprint "eagle-import:C0603")
      (libsource (lib "eagle-import") (part "C-EUC0603"))
    )
    (comp (ref "C38")
      (value "1µ/25V")
      (footprint "eagle-import:SMC_A")
      (libsource (lib "eagle-import") (part "CPOL-EUSMCA"))
    )
    (comp (ref "C42")
      (value "47µ/35V")
      (footprint "eagle-import:PANASONIC_D")
      (libsource (lib "eagle-import") (part "CPOL-EUD"))
    )
    (comp (ref "C43")
      (value "100n")
      (footprint "eagle-import:C0603")
      (libsource (lib "eagle-import") (part "C-EUC0603"))
    )
    (comp (ref "C46")
      (value "100n")
      (footprint "eagle-import:C0603")
      (libsource (lib "eagle-import") (part "C-EUC0603"))
    )
    (comp (ref "C51")
      (value "100n")
      (footprint "eagle-import:C0603")
      (libsource (lib "eagle-import") (part "C-EUC0603"))
    )
    (comp (ref "D12")
      (value "BZX84-A5V1")
      (footprint "eagle-import:TO236")
      (libsource (lib "eagle-import") (part "BZX84CSMD"))
    )
    (comp (ref "IC1")
      (value "LM1458D")
      (footprint "eagle-import:SO08")
      (libsource (lib "eagle-import") (part "1458DLM"))
    )
    (comp (ref "LED1")
      (value "LEDCHIP-LED0805")
      (footprint "eagle-import:CHIP-LED0805")
      (libsource (lib "eagle-import") (part "LEDCHIP-LED0805"))
    )
    (comp (ref "LED2")
      (value "LEDCHIP-LED0805")
      (footprint "eagle-import:CHIP-LED0805")
      (libsource (lib "eagle-import") (part "LEDCHIP-LED0805"))
    )
    (comp (ref "LED3")
      (value "LEDCHIP-LED0805")
      (footprint "eagle-import:CHIP-LED0805")
      (libsource (lib "eagle-import") (part "LEDCHIP-LED0805"))
    )
    (comp (ref "LED9")
      (value "LEDCHIP-LED0805")
      (footprint "eagle-import:CHIP-LED0805")
      (libsource (lib "eagle-import") (part "LEDCHIP-LED0805"))
    )
    (comp (ref "OK1")
      (value "ILD213")
      (footprint "eagle-import:SOIC08")
      (libsource (lib "eagle-import") (part "ILD213"))
    )
    (comp (ref "OK2")
      (value "ILD213")
      (footprint "eagle-import:SOIC08")
      (libsource (lib "eagle-import") (part "ILD213"))
    )
    (comp (ref "R4")
      (value "24k, 1%")
      (footprint "eagle-import:R0805")
      (libsource (lib "eagle-import") (part "R-EU_R0805"))
    )
    (comp (ref "R6")
      (value "12k, 1%")
      (footprint "eagle-import:R0805")
      (libsource (lib "eagle-import") (part "R-EU_R0805"))
    )
    (comp (ref "R7")
      (value "5.6k, 1%")
      (footprint "eagle-import:R0805")
      (libsource (lib "eagle-import") (part "R-EU_R0805"))
    )
    (comp (ref "R8")
      (value "10k, 1%")
      (footprint "eagle-import:R0805")
      (libsource (lib "eagle-import") (part "R-EU_R0805"))
    )
    (comp (ref "R9")
      (value "2k")
      (footprint "eagle-import:R0805")
      (libsource (lib "eagle-import") (part "R-EU_R0805"))
    )
    (comp (ref "R10")
      (value "5,6k")
      (footprint "eagle-import:R0805")
      (libsource (lib "eagle-import") (part "R-EU_R0805"))
    )
    (comp (ref "R11")
      (value "10k, 1%")
      (footprint "eagle-import:R0805")
      (libsource (lib "eagle-import") (part "R-EU_R0805"))
    )
    (comp (ref "R29")
      (value "1k")
      (footprint "eagle-import:R0805")
      (libsource (lib "eagle-import") (part "R-EU_R0805"))
    )
    (comp (ref "R33")
      (value "1M")
      (footprint "eagle-import:R2512")
      (libsource (lib "eagle-import") (part "R-EU_R2512"))
    )
    (comp (ref "R34")
      (value "1M")
      (footprint "eagle-import:R2512")
      (libsource (lib "eagle-import") (part "R-EU_R2512"))
    )
    (comp (ref "R35")
      (value "1M")
      (footprint "eagle-import:R2512")
      (libsource (lib "eagle-import") (part "R-EU_R2512"))
    )
    (comp (ref "R36")
      (value "50k")
      (footprint "eagle-import:R0805")
      (libsource (lib "eagle-import") (part "R-EU_R0805"))
    )
    (comp (ref "R37")
      (value "16.9k")
      (footprint "eagle-import:R0805")
      (libsource (lib "eagle-import") (part "R-EU_R0805"))
    )
    (comp (ref "R38")
      (value "7.68k")
      (footprint "eagle-import:R0805")
      (libsource (lib "eagle-import") (part "R-EU_R0805"))
    )
    (comp (ref "R39")
      (value "4.7k")
      (footprint "eagle-import:R0805")
      (libsource (lib "eagle-import") (part "R-EU_R0805"))
    )
    (comp (ref "R40")
      (value "4.7k")
      (footprint "eagle-import:R0805")
      (libsource (lib "eagle-import") (part "R-EU_R0805"))
    )
    (comp (ref "R41")
      (value "4.7k")
      (footprint "eagle-import:R0805")
      (libsource (lib "eagle-import") (part "R-EU_R0805"))
    )
    (comp (ref "R49")
      (value "4.7k")
      (footprint "eagle-import:R0805")
      (libsource (lib "eagle-import") (part "R-EU_R0805"))
    )
    (comp (ref "R101")
      (value "1M, 1%")
      (footprint "eagle-import:R2512")
      (libsource (lib "eagle-import") (part "R-EU_R2512"))
    )
    (comp (ref "R105")
      (value "680")
      (footprint "eagle-import:R0805")
      (libsource (lib "eagle-import") (part "R-EU_R0805"))
    )
    (comp (ref "U$4")
      (value "TMH-D")
      (footprint "eagle-import:TMH-D")
      (libsource (lib "eagle-import") (part "TMH-D"))
    )
    (comp (ref "VR1")
      (value "TL431_SOT23")
      (footprint "eagle-import:SOT23")
      (libsource (lib "eagle-import") (part "TL431_SOT23"))
    )
    (comp (ref "VR2")
      (value "TL431_SOT23")
      (footprint "eagle-import:SOT23")
      (libsource (lib "eagle-import") (part "TL431_SOT23"))
    )
    (comp (ref "VR3")
      (value "TL431_SOT23")
      (footprint "eagle-import:SOT23")
      (libsource (lib "eagle-import") (part "TL431_SOT23"))
    )
    (comp (ref "C33")
      (value "100n")
      (footprint "eagle-import:C0603")
      (libsource (lib "eagle-import") (part "C-EUC0603"))
    )
    (comp (ref "C34")
      (value "100n")
      (footprint "eagle-import:C0603")
      (libsource (lib "eagle-import") (part "C-EUC0603"))
    )
    (comp (ref "C36")
      (value "100n")
      (footprint "eagle-import:C0603")
      (libsource (lib "eagle-import") (part "C-EUC0603"))
    )
    (comp (ref "C37")
      (value "1µ/25V")
      (footprint "eagle-import:SMC_A")
      (libsource (lib "eagle-import") (part "CPOL-EUSMCA"))
    )
    (comp (ref "C39")
      (value "100n")
      (footprint "eagle-import:C0603")
      (libsource (lib "eagle-import") (part "C-EUC0603"))
    )
    (comp (ref "C41")
      (value "100n")
      (footprint "eagle-import:C0603")
      (libsource (lib "eagle-import") (part "C-EUC0603"))
    )
    (comp (ref "C44")
      (value "100n")
      (footprint "eagle-import:C0603")
      (libsource (lib "eagle-import") (part "C-EUC0603"))
    )
    (comp (ref "C45")
      (value "100n")
      (footprint "eagle-import:C0603")
      (libsource (lib "eagle-import") (part "C-EUC0603"))
    )
    (comp (ref "C47")
      (value "100n")
      (footprint "eagle-import:C0603")
      (libsource (lib "eagle-import") (part "C-EUC0603"))
    )
    (comp (ref "D14")
      (value "BZX84-A5V1")
      (footprint "eagle-import:TO236")
      (libsource (lib "eagle-import") (part "BZX84CSMD"))
    )
    (comp (ref "IC2")
      (value "4043D")
      (footprint "eagle-import:SO16")
      (libsource (lib "eagle-import") (part "4043D"))
    )
    (comp (ref "IC4")
      (value "LM1458D")
      (footprint "eagle-import:SO08")
      (libsource (lib "eagle-import") (part "1458DLM"))
    )
    (comp (ref "R5")
      (value "10k, 1%")
      (footprint "eagle-import:R0805")
      (libsource (lib "eagle-import") (part "R-EU_R0805"))
    )
    (comp (ref "R21")
      (value "33k, 1%")
      (footprint "eagle-import:R0805")
      (libsource (lib "eagle-import") (part "R-EU_R0805"))
    )
    (comp (ref "R22")
      (value "10k")
      (footprint "eagle-import:R0805")
      (libsource (lib "eagle-import") (part "R-EU_R0805"))
    )
    (comp (ref "R25")
      (value "100k")
      (footprint "eagle-import:R0805")
      (libsource (lib "eagle-import") (part "R-EU_R0805"))
    )
    (comp (ref "R26")
      (value "50k")
      (footprint "eagle-import:R0805")
      (libsource (lib "eagle-import") (part "R-EU_R0805"))
    )
    (comp (ref "R30")
      (value "3.3k")
      (footprint "eagle-import:R0805")
      (libsource (lib "eagle-import") (part "R-EU_R0805"))
    )
    (comp (ref "R52")
      (value "5,6k, 1%")
      (footprint "eagle-import:R0805")
      (libsource (lib "eagle-import") (part "R-EU_R0805"))
    )
    (comp (ref "R58")
      (value "10k")
      (footprint "eagle-import:R0805")
      (libsource (lib "eagle-import") (part "R-EU_R0805"))
    )
    (comp (ref "S1")
      (value "10-XX")
      (footprint "eagle-import:B3F-10XX")
      (libsource (lib "eagle-import") (part "10-XX"))
    )
    (comp (ref "T4")
      (value "BC849")
      (footprint "eagle-import:SOT23")
      (libsource (lib "eagle-import") (part "BC849"))
    )
    (comp (ref "U2")
      (value "SN74LVC2G02DCTR")
      (footprint "eagle-import:SOP65P400X130-8N")
      (libsource (lib "eagle-import") (part "SN74LVC2G02DCTR"))
    )
  )
  (nets
    (net (code "1") (name "+3V3") (class "Default")
      (node (ref "C2") (pin "1") (pinfunction "1_1") (pintype "passive"))
      (node (ref "C27") (pin "1") (pinfunction "1_1") (pintype "passive"))
      (node (ref "D2") (pin "A") (pinfunction "A_A") (pintype "passive"))
      (node (ref "IC3") (pin "2") (pinfunction "OUT_2") (pintype "passive"))
      (node (ref "IC3") (pin "4") (pinfunction "OUT_4") (pintype "input"))
      (node (ref "JP2") (pin "4") (pinfunction "4_4") (pintype "passive"))
      (node (ref "R42") (pin "2") (pinfunction "2_2") (pintype "passive"))
      (node (ref "U1") (pin "10") (pinfunction "OE_10") (pintype "input"))
      (node (ref "U1") (pin "2") (pinfunction "VCCA_2") (pintype "power_in"))
    )
    (net (code "2") (name "+5V") (class "Default")
      (node (ref "C1") (pin "1") (pinfunction "1_1") (pintype "passive"))
      (node (ref "C18") (pin "+") (pinfunction "+_+") (pintype "passive"))
      (node (ref "C26") (pin "1") (pinfunction "1_1") (pintype "passive"))
      (node (ref "C28") (pin "1") (pinfunction "1_1") (pintype "passive"))
      (node (ref "C34") (pin "1") (pinfunction "1_1") (pintype "passive"))
      (node (ref "C44") (pin "1") (pinfunction "1_1") (pintype "passive"))
      (node (ref "C45") (pin "1") (pinfunction "1_1") (pintype "passive"))
      (node (ref "C8") (pin "2") (pinfunction "2_2") (pintype "passive"))
      (node (ref "D2") (pin "K") (pinfunction "C_K") (pintype "passive"))
      (node (ref "IC2") (pin "16") (pinfunction "VDD_16") (pintype "power_in"))
      (node (ref "IC3") (pin "3") (pinfunction "IN_3") (pintype "input"))
      (node (ref "IC4") (pin "8") (pinfunction "V+_8") (pintype "power_in"))
      (node (ref "L5") (pin "1") (pinfunction "1_1") (pintype "passive"))
      (node (ref "OK2") (pin "8") (pinfunction "COL_8") (pintype "passive"))
      (node (ref "R17") (pin "2") (pinfunction "2_2") (pintype "passive"))
      (node (ref "R26") (pin "2") (pinfunction "2_2") (pintype "passive"))
      (node (ref "R43") (pin "2") (pinfunction "2_2") (pintype "passive"))
      (node (ref "R58") (pin "2") (pinfunction "2_2") (pintype "passive"))
      (node (ref "R70") (pin "1") (pinfunction "1_1") (pintype "passive"))
      (node (ref "S1") (pin "1") (pinfunction "S_1") (pintype "passive"))
      (node (ref "S1") (pin "2") (pinfunction "S1_2") (pintype "passive"))
      (node (ref "SV1") (pin "2") (pinfunction "2_2") (pintype "passive"))
      (node (ref "U$1") (pin "3") (pinfunction "VDD_3") (pintype "power_in"))
      (node (ref "U$2") (pin "4") (pinfunction "VCC_4") (pintype "bidirectional"))
      (node (ref "U1") (pin "19") (pinfunction "VCCB_19") (pintype "power_in"))
      (node (ref "U2") (pin "8") (pinfunction "VCC_8") (pintype "power_in"))
      (node (ref "U3") (pin "4") (pinfunction "FB_4") (pintype "input"))
    )
    (net (code "3") (name "+5V{slash}1") (class "Default")
      (node (ref "C40") (pin "+") (pinfunction "+_+") (pintype "passive"))
      (node (ref "JP3") (pin "2") (pinfunction "2_2") (pintype "passive"))
      (node (ref "JP4") (pin "2") (pinfunction "2_2") (pintype "passive"))
      (node (ref "L1") (pin "1") (pinfunction "1_1") (pintype "passive"))
      (node (ref "R45") (pin "2") (pinfunction "2_2") (pintype "passive"))
      (node (ref "U$8") (pin "4") (pinfunction "FB_4") (pintype "bidirectional"))
    )
    (net (code "4") (name "+5V{slash}3") (class "Default")
      (node (ref "C37") (pin "+") (pinfunction "+_+") (pintype "passive"))
      (node (ref "C39") (pin "1") (pinfunction "1_1") (pintype "passive"))
      (node (ref "C7") (pin "2") (pinfunction "2_2") (pintype "passive"))
      (node (ref "D14") (pin "C") (pinfunction "C_C") (pintype "passive"))
      (node (ref "OK1") (pin "6") (pinfunction "COL_6") (pintype "passive"))
      (node (ref "R30") (pin "1") (pinfunction "1_1") (pintype "passive"))
      (node (ref "R5") (pin "2") (pinfunction "2_2") (pintype "passive"))
      (node (ref "U$2") (pin "19") (pinfunction "AVCC_19") (pintype "bidirectional"))
    )
    (net (code "5") (name "+5V{slash}4") (class "Default")
      (node (ref "C16") (pin "1") (pinfunction "1_1") (pintype "passive"))
      (node (ref "C38") (pin "+") (pinfunction "+_+") (pintype "passive"))
      (node (ref "D12") (pin "C") (pinfunction "C_C") (pintype "passive"))
      (node (ref "OK1") (pin "8") (pinfunction "COL_8") (pintype "passive"))
      (node (ref "R29") (pin "1") (pinfunction "1_1") (pintype "passive"))
      (node (ref "R7") (pin "2") (pinfunction "2_2") (pintype "passive"))
    )
    (net (code "6") (name "+12V") (class "Default")
      (node (ref "C21") (pin "+") (pinfunction "+_+") (pintype "passive"))
      (node (ref "L6") (pin "1") (pinfunction "1_1") (pintype "passive"))
      (node (ref "R44") (pin "2") (pinfunction "2_2") (pintype "passive"))
      (node (ref "U4") (pin "4") (pinfunction "FB_4") (pintype "input"))
    )
    (net (code "7") (name "+24V") (class "Default")
      (node (ref "C17") (pin "+") (pinfunction "+_+") (pintype "passive"))
      (node (ref "C20") (pin "+") (pinfunction "+_+") (pintype "passive"))
      (node (ref "C3") (pin "+") (pinfunction "+_+") (pintype "passive"))
      (node (ref "C42") (pin "+") (pinfunction "+_+") (pintype "passive"))
      (node (ref "D1") (pin "K") (pinfunction "C_K") (pintype "passive"))
      (node (ref "F1") (pin "1") (pinfunction "1_1") (pintype "passive"))
      (node (ref "R30") (pin "2") (pinfunction "2_2") (pintype "passive"))
      (node (ref "R31") (pin "1") (pinfunction "1_1") (pintype "passive"))
      (node (ref "U$4") (pin "1") (pinfunction "U_IN_1") (pintype "bidirectional"))
      (node (ref "U$8") (pin "1") (pinfunction "VIN_1") (pintype "bidirectional"))
      (node (ref "U3") (pin "7") (pinfunction "VIN_7") (pintype "power_in"))
      (node (ref "U4") (pin "7") (pinfunction "VIN_7") (pintype "power_in"))
    )
    (net (code "8") (name "24V_PRI") (class "Default")
      (node (ref "C10") (pin "+") (pinfunction "+_+") (pintype "passive"))
      (node (ref "C35") (pin "1") (pinfunction "1_1") (pintype "passive"))
      (node (ref "C50") (pin "1") (pinfunction "1_1") (pintype "passive"))
      (node (ref "C9") (pin "+") (pinfunction "+_+") (pintype "passive"))
      (node (ref "Q3") (pin "D") (pinfunction "D_D") (pintype "passive"))
      (node (ref "Q5") (pin "4") (pinfunction "D_4") (pintype "passive"))
      (node (ref "R23") (pin "2") (pinfunction "2_2") (pintype "passive"))
      (node (ref "R27") (pin "2") (pinfunction "2_2") (pintype "passive"))
    )
    (net (code "9") (name "ACTIVATE_BOOSTER") (class "Default")
      (node (ref "R24") (pin "1") (pinfunction "1_1") (pintype "passive"))
      (node (ref "R25") (pin "1") (pinfunction "1_1") (pintype "passive"))
      (node (ref "U$2") (pin "26") (pinfunction "PB5_26") (pintype "bidirectional"))
    )
    (net (code "10") (name "ACTIVATE_SERVO") (class "Default")
      (node (ref "R47") (pin "1") (pinfunction "1_1") (pintype "passive"))
      (node (ref "U$2") (pin "15") (pinfunction "PD7_15") (pintype "bidirectional"))
    )
    (net (code "11") (name "ADC9{slash}FREI") (class "Default")
      (node (ref "U$2") (pin "18") (pinfunction "PC5_18") (pintype "bidirectional"))
    )
    (net (code "12") (name "ADC_24V_LOGIK{slash}SCK_A") (class "Default")
      (node (ref "R31") (pin "2") (pinfunction "2_2") (pintype "passive"))
      (node (ref "R50") (pin "1") (pinfunction "1_1") (pintype "passive"))
      (node (ref "SV1") (pin "7") (pinfunction "7_7") (pintype "passive"))
      (node (ref "U$2") (pin "12") (pinfunction "(RXD)PD4_12") (pintype "bidirectional"))
    )
    (net (code "13") (name "ADC_24V_PRI") (class "Default")
      (node (ref "R27") (pin "1") (pinfunction "1_1") (pintype "passive"))
      (node (ref "R28") (pin "2") (pinfunction "2_2") (pintype "passive"))
      (node (ref "U$2") (pin "13") (pinfunction "PD5_13") (pintype "bidirectional"))
    )
    (net (code "14") (name "ADC_CAP") (class "Default")
      (node (ref "C23") (pin "1") (pinfunction "1_1") (pintype "passive"))
      (node (ref "C47") (pin "1") (pinfunction "1_1") (pintype "passive"))
      (node (ref "IC4") (pin "3") (pinfunction "+IN_3") (pintype "input"))
      (node (ref "OK1") (pin "5") (pinfunction "EMIT_5") (pintype "passive"))
      (node (ref "R8") (pin "2") (pinfunction "2_2") (pintype "passive"))
      (node (ref "U$2") (pin "14") (pinfunction "PD6_14") (pintype "bidirectional"))
    )
    (net (code "15") (name "BOOSTER_24V") (class "Default")
      (node (ref "Q5") (pin "3") (pinfunction "S_3") (pintype "passive"))
      (node (ref "R200") (pin "2") (pinfunction "2_2") (pintype "passive"))
      (node (ref "R23") (pin "1") (pinfunction "1_1") (pintype "passive"))
      (node (ref "R46") (pin "2") (pinfunction "2_2") (pintype "passive"))
      (node (ref "X2") (pin "2") (pinfunction "KL_2") (pintype "passive"))
    )
    (net (code "16") (name "CAN_H") (class "Default")
      (node (ref "RJ_1") (pin "P$3") (pinfunction "P$3_P$3") (pintype "bidirectional"))
      (node (ref "RJ_2") (pin "P$3") (pinfunction "P$3_P$3") (pintype "bidirectional"))
      (node (ref "SJ1") (pin "2") (pinfunction "2_2") (pintype "passive"))
      (node (ref "U$1") (pin "7") (pinfunction "CANH_7") (pintype "bidirectional"))
    )
    (net (code "17") (name "CAN_L") (class "Default")
      (node (ref "R32") (pin "2") (pinfunction "2_2") (pintype "passive"))
      (node (ref "RJ_1") (pin "P$2") (pinfunction "P$2_P$2") (pintype "bidirectional"))
      (node (ref "RJ_2") (pin "P$2") (pinfunction "P$2_P$2") (pintype "bidirectional"))
      (node (ref "U$1") (pin "6") (pinfunction "CANL_6") (pintype "bidirectional"))
    )
    (net (code "18") (name "CAN_RX") (class "Default")
      (node (ref "U$1") (pin "4") (pinfunction "RXD_4") (pintype "output"))
      (node (ref "U$2") (pin "7") (pinfunction "(RXCAN)PC3_7") (pintype "bidirectional"))
    )
    (net (code "19") (name "CAN_TX") (class "Default")
      (node (ref "U$1") (pin "1") (pinfunction "TXD_1") (pintype "input"))
      (node (ref "U$2") (pin "6") (pinfunction "(TXCAN)PC2_6") (pintype "bidirectional"))
    )
    (net (code "20") (name "CAP_+12V") (class "Default")
      (node (ref "C29") (pin "+") (pinfunction "+_+") (pintype "passive"))
      (node (ref "C30") (pin "+") (pinfunction "+_+") (pintype "passive"))
      (node (ref "C31") (pin "+") (pinfunction "+_+") (pintype "passive"))
      (node (ref "C43") (pin "1") (pinfunction "1_1") (pintype "passive"))
      (node (ref "IC1") (pin "8") (pinfunction "V+_8") (pintype "power_in"))
      (node (ref "R29") (pin "2") (pinfunction "2_2") (pintype "passive"))
      (node (ref "R39") (pin "2") (pinfunction "2_2") (pintype "passive"))
      (node (ref "R40") (pin "2") (pinfunction "2_2") (pintype "passive"))
      (node (ref "R41") (pin "2") (pinfunction "2_2") (pintype "passive"))
      (node (ref "R49") (pin "2") (pinfunction "2_2") (pintype "passive"))
      (node (ref "T6") (pin "E") (pinfunction "E_E") (pintype "passive"))
      (node (ref "U$4") (pin "6") (pinfunction "+U_OUT_6") (pintype "bidirectional"))
      (node (ref "U$5") (pin "8") (pinfunction "VDD_8") (pintype "bidirectional"))
      (node (ref "U$6") (pin "8") (pinfunction "VDD_8") (pintype "bidirectional"))
    )
    (net (code "21") (name "CAP_0V") (class "Default")
      (node (ref "C14") (pin "2") (pinfunction "2_2") (pintype "passive"))
      (node (ref "C15") (pin "2") (pinfunction "2_2") (pintype "passive"))
      (node (ref "C16") (pin "2") (pinfunction "2_2") (pintype "passive"))
      (node (ref "C25") (pin "-") (pinfunction "-_-") (pintype "passive"))
      (node (ref "C29") (pin "-") (pinfunction "-_-") (pintype "passive"))
      (node (ref "C30") (pin "-") (pinfunction "-_-") (pintype "passive"))
      (node (ref "C31") (pin "-") (pinfunction "-_-") (pintype "passive"))
      (node (ref "C32") (pin "2") (pinfunction "2_2") (pintype "passive"))
      (node (ref "C38") (pin "-") (pinfunction "-_-") (pintype "passive"))
      (node (ref "C43") (pin "2") (pinfunction "2_2") (pintype "passive"))
      (node (ref "C46") (pin "2") (pinfunction "2_2") (pintype "passive"))
      (node (ref "C51") (pin "2") (pinfunction "2_2") (pintype "passive"))
      (node (ref "CAP_0V") (pin "P$1") (pinfunction "P_P$1") (pintype "passive"))
      (node (ref "D10") (pin "A") (pinfunction "A_A") (pintype "passive"))
      (node (ref "D11") (pin "A") (pinfunction "A_A") (pintype "passive"))
      (node (ref "D12") (pin "A") (pinfunction "A_A") (pintype "passive"))
      (node (ref "H1") (pin "B3,0") (pinfunction "MOUNT_B3,0") (pintype "passive"))
      (node (ref "IC1") (pin "4") (pinfunction "V-_4") (pintype "power_in"))
      (node (ref "LED9") (pin "C") (pinfunction "C_C") (pintype "passive"))
      (node (ref "OK1") (pin "4") (pinfunction "C_4") (pintype "passive"))
      (node (ref "OK2") (pin "2") (pinfunction "C_2") (pintype "passive"))
      (node (ref "Q2") (pin "S") (pinfunction "S_S") (pintype "passive"))
      (node (ref "Q6") (pin "S") (pinfunction "S_S") (pintype "passive"))
      (node (ref "R11") (pin "1") (pinfunction "1_1") (pintype "passive"))
      (node (ref "R12") (pin "1") (pinfunction "1_1") (pintype "passive"))
      (node (ref "R20") (pin "1") (pinfunction "1_1") (pintype "passive"))
      (node (ref "R36") (pin "1") (pinfunction "1_1") (pintype "passive"))
      (node (ref "R37") (pin "1") (pinfunction "1_1") (pintype "passive"))
      (node (ref "R38") (pin "1") (pinfunction "1_1") (pintype "passive"))
      (node (ref "R4") (pin "1") (pinfunction "1_1") (pintype "passive"))
      (node (ref "R6") (pin "1") (pinfunction "1_1") (pintype "passive"))
      (node (ref "U$4") (pin "4") (pinfunction "-U_OUT_4") (pintype "bidirectional"))
      (node (ref "U$5") (pin "5") (pinfunction "GND_5") (pintype "bidirectional"))
      (node (ref "U$6") (pin "5") (pinfunction "GND_5") (pintype "bidirectional"))
      (node (ref "VR1") (pin "3") (pinfunction "A_3") (pintype "passive"))
      (node (ref "VR2") (pin "3") (pinfunction "A_3") (pintype "passive"))
      (node (ref "VR3") (pin "3") (pinfunction "A_3") (pintype "passive"))
    )
    (net (code "22") (name "CAP_330V") (class "Default")
      (node (ref "C25") (pin "+") (pinfunction "+_+") (pintype "passive"))
      (node (ref "CAP_330V") (pin "P$1") (pinfunction "P_P$1") (pintype "passive"))
      (node (ref "COIL_OUT") (pin "P$1") (pinfunction "P_P$1") (pintype "passive"))
      (node (ref "D8") (pin "K") (pinfunction "C_K") (pintype "passive"))
      (node (ref "D9") (pin "K") (pinfunction "C_K") (pintype "passive"))
      (node (ref "R101") (pin "2") (pinfunction "2_2") (pintype "passive"))
      (node (ref "R2") (pin "1") (pinfunction "1_1") (pintype "passive"))
      (node (ref "R33") (pin "2") (pinfunction "2_2") (pintype "passive"))
      (node (ref "R34") (pin "2") (pinfunction "2_2") (pintype "passive"))
      (node (ref "R35") (pin "2") (pinfunction "2_2") (pintype "passive"))
      (node (ref "U$7") (pin "C") (pinfunction "C_C") (pintype "passive"))
    )
    (net (code "23") (name "CLKOUT_ETH") (class "Default")
      (node (ref "U1") (pin "12") (pinfunction "B8_12") (pintype "bidirectional"))
    )
    (net (code "24") (name "CLKOUT_ETH_3V") (class "Default")
      (node (ref "JP2") (pin "1") (pinfunction "1_1") (pintype "passive"))
      (node (ref "U1") (pin "9") (pinfunction "A8_9") (pintype "bidirectional"))
    )
    (net (code "25") (name "CS_ETH") (class "Default")
      (node (ref "U$2") (pin "29") (pinfunction "PD0_29") (pintype "bidirectional"))
      (node (ref "U1") (pin "13") (pinfunction "B7_13") (pintype "bidirectional"))
    )
    (net (code "26") (name "CS_ETH_3V") (class "Default")
      (node (ref "JP2") (pin "2") (pinfunction "2_2") (pintype "passive"))
      (node (ref "U1") (pin "8") (pinfunction "A7_8") (pintype "bidirectional"))
    )
    (net (code "27") (name "D2A") (class "Default")
      (node (ref "R52") (pin "1") (pinfunction "1_1") (pintype "passive"))
      (node (ref "U$2") (pin "25") (pinfunction "PC7_25") (pintype "bidirectional"))
    )
    (net (code "28") (name "FREI") (class "Default")
      (node (ref "U$2") (pin "16") (pinfunction "PB2_16") (pintype "bidirectional"))
    )
    (net (code "29") (name "FREI2") (class "Default")
      (node (ref "U$2") (pin "27") (pinfunction "PB6_27") (pintype "bidirectional"))
    )
    (net (code "30") (name "GND") (class "Default")
      (node (ref "C1") (pin "2") (pinfunction "2_2") (pintype "passive"))
      (node (ref "C17") (pin "-") (pinfunction "-_-") (pintype "passive"))
      (node (ref "C18") (pin "-") (pinfunction "-_-") (pintype "passive"))
      (node (ref "C2") (pin "2") (pinfunction "2_2") (pintype "passive"))
      (node (ref "C20") (pin "-") (pinfunction "-_-") (pintype "passive"))
      (node (ref "C21") (pin "-") (pinfunction "-_-") (pintype "passive"))
      (node (ref "C23") (pin "2") (pinfunction "2_2") (pintype "passive"))
      (node (ref "C24") (pin "2") (pinfunction "2_2") (pintype "passive"))
      (node (ref "C26") (pin "2") (pinfunction "2_2") (pintype "passive"))
      (node (ref "C27") (pin "2") (pinfunction "2_2") (pintype "passive"))
      (node (ref "C28") (pin "2") (pinfunction "2_2") (pintype "passive"))
      (node (ref "C3") (pin "-") (pinfunction "-_-") (pintype "passive"))
      (node (ref "C33") (pin "2") (pinfunction "2_2") (pintype "passive"))
      (node (ref "C34") (pin "2") (pinfunction "2_2") (pintype "passive"))
      (node (ref "C36") (pin "2") (pinfunction "2_2") (pintype "passive"))
      (node (ref "C37") (pin "-") (pinfunction "-_-") (pintype "passive"))
      (node (ref "C39") (pin "2") (pinfunction "2_2") (pintype "passive"))
      (node (ref "C4") (pin "1") (pinfunction "1_1") (pintype "passive"))
      (node (ref "C40") (pin "-") (pinfunction "-_-") (pintype "passive"))
      (node (ref "C41") (pin "2") (pinfunction "2_2") (pintype "passive"))
      (node (ref "C42") (pin "-") (pinfunction "-_-") (pintype "passive"))
      (node (ref "C44") (pin "2") (pinfunction "2_2") (pintype "passive"))
      (node (ref "C45") (pin "2") (pinfunction "2_2") (pintype "passive"))
      (node (ref "C47") (pin "2") (pinfunction "2_2") (pintype "passive"))
      (node (ref "C5") (pin "1") (pinfunction "1_1") (pintype "passive"))
      (node (ref "C6") (pin "1") (pinfunction "1_1") (pintype "passive"))
      (node (ref "C7") (pin "1") (pinfunction "1_1") (pintype "passive"))
      (node (ref "C8") (pin "1") (pinfunction "1_1") (pintype "passive"))
      (node (ref "D1") (pin "A") (pinfunction "A_A") (pintype "passive"))
      (node (ref "D14") (pin "A") (pinfunction "A_A") (pintype "passive"))
      (node (ref "D15") (pin "A") (pinfunction "A_A") (pintype "passive"))
      (node (ref "D6") (pin "A") (pinfunction "A_A") (pintype "passive"))
      (node (ref "D7") (pin "A") (pinfunction "A_A") (pintype "passive"))
      (node (ref "H2") (pin "B3,0") (pinfunction "MOUNT_B3,0") (pintype "passive"))
      (node (ref "H3") (pin "B3,0") (pinfunction "MOUNT_B3,0") (pintype "passive"))
      (node (ref "H4") (pin "B3,0") (pinfunction "MOUNT_B3,0") (pintype "passive"))
      (node (ref "IC2") (pin "3") (pinfunction "R0_3") (pintype "input"))
      (node (ref "IC2") (pin "4") (pinfunction "S0_4") (pintype "input"))
      (node (ref "IC2") (pin "6") (pinfunction "S1_6") (pintype "input"))
      (node (ref "IC2") (pin "7") (pinfunction "R1_7") (pintype "input"))
      (node (ref "IC2") (pin "8") (pinfunction "VSS_8") (pintype "power_in"))
      (node (ref "IC3") (pin "1") (pinfunction "GND_1") (pintype "input"))
      (node (ref "IC4") (pin "4") (pinfunction "V-_4") (pintype "power_in"))
      (node (ref "IC4") (pin "5") (pinfunction "+IN_5") (pintype "input"))
      (node (ref "IC4") (pin "6") (pinfunction "-IN_6") (pintype "input"))
      (node (ref "JP2") (pin "5") (pinfunction "5_5") (pintype "passive"))
      (node (ref "JP4") (pin "3") (pinfunction "3_3") (pintype "passive"))
      (node (ref "LED10") (pin "C") (pinfunction "C_C") (pintype "passive"))
      (node (ref "LED4") (pin "C") (pinfunction "C_C") (pintype "passive"))
      (node (ref "LED5") (pin "C") (pinfunction "C_C") (pintype "passive"))
      (node (ref "LED6") (pin "C") (pinfunction "C_C") (pintype "passive"))
      (node (ref "LED7") (pin "C") (pinfunction "C_C") (pintype "passive"))
      (node (ref "R1") (pin "1") (pinfunction "1_1") (pintype "passive"))
      (node (ref "R10") (pin "1") (pinfunction "1_1") (pintype "passive"))
      (node (ref "R16") (pin "1") (pinfunction "1_1") (pintype "passive"))
      (node (ref "R21") (pin "1") (pinfunction "1_1") (pintype "passive"))
      (node (ref "R22") (pin "1") (pinfunction "1_1") (pintype "passive"))
      (node (ref "R28") (pin "1") (pinfunction "1_1") (pintype "passive"))
      (node (ref "R50") (pin "2") (pinfunction "2_2") (pintype "passive"))
      (node (ref "R51") (pin "1") (pinfunction "1_1") (pintype "passive"))
      (node (ref "R8") (pin "1") (pinfunction "1_1") (pintype "passive"))
      (node (ref "RJ_1") (pin "P$4") (pinfunction "P$4_P$4") (pintype "bidirectional"))
      (node (ref "RJ_2") (pin "P$4") (pinfunction "P$4_P$4") (pintype "bidirectional"))
      (node (ref "SV1") (pin "10") (pinfunction "10_10") (pintype "passive"))
      (node (ref "SV1") (pin "4") (pinfunction "4_4") (pintype "passive"))
      (node (ref "SV1") (pin "6") (pinfunction "6_6") (pintype "passive"))
      (node (ref "SV1") (pin "8") (pinfunction "8_8") (pintype "passive"))
      (node (ref "T2") (pin "2") (pinfunction "E_2") (pintype "passive"))
      (node (ref "T4") (pin "2") (pinfunction "E_2") (pintype "passive"))
      (node (ref "T5") (pin "2") (pinfunction "S_2") (pintype "passive"))
      (node (ref "U$1") (pin "2") (pinfunction "VSS_2") (pintype "passive"))
      (node (ref "U$2") (pin "20") (pinfunction "AGND_20") (pintype "power_in"))
      (node (ref "U$2") (pin "5") (pinfunction "GND_5") (pintype "power_in"))
      (node (ref "U$4") (pin "2") (pinfunction "GND_2") (pintype "bidirectional"))
      (node (ref "U$5") (pin "1") (pinfunction "NC_1") (pintype "bidirectional"))
      (node (ref "U$5") (pin "3") (pinfunction "CATHODE_3") (pintype "bidirectional"))
      (node (ref "U$5") (pin "4") (pinfunction "NC_4") (pintype "bidirectional"))
      (node (ref "U$6") (pin "1") (pinfunction "NC_1") (pintype "bidirectional"))
      (node (ref "U$6") (pin "4") (pinfunction "NC_4") (pintype "bidirectional"))
      (node (ref "U$8") (pin "3") (pinfunction "GND_3") (pintype "bidirectional"))
      (node (ref "U$8") (pin "5") (pinfunction "~{ON}/OFF_5") (pintype "bidirectional"))
      (node (ref "U1") (pin "11") (pinfunction "GND_11") (pintype "passive"))
      (node (ref "U2") (pin "4") (pinfunction "GND_4") (pintype "passive"))
      (node (ref "U3") (pin "6") (pinfunction "GND_6") (pintype "passive"))
      (node (ref "U4") (pin "6") (pinfunction "GND_6") (pintype "passive"))
      (node (ref "X1") (pin "2") (pinfunction "KL_2") (pintype "passive"))
    )
    (net (code "31") (name "GND1") (class "Default")
      (node (ref "C10") (pin "-") (pinfunction "-_-") (pintype "passive"))
      (node (ref "C35") (pin "2") (pinfunction "2_2") (pintype "passive"))
      (node (ref "C50") (pin "2") (pinfunction "2_2") (pintype "passive"))
      (node (ref "C9") (pin "-") (pinfunction "-_-") (pintype "passive"))
      (node (ref "LED8") (pin "C") (pinfunction "C_C") (pintype "passive"))
      (node (ref "T3") (pin "2") (pinfunction "E_2") (pintype "passive"))
      (node (ref "X2") (pin "1") (pinfunction "KL_1") (pintype "passive"))
    )
    (net (code "32") (name "INT_ETH") (class "Default")
      (node (ref "U$2") (pin "30") (pinfunction "PC0_30") (pintype "bidirectional"))
      (node (ref "U1") (pin "20") (pinfunction "B1_20") (pintype "bidirectional"))
    )
    (net (code "33") (name "INT_ETH_3V") (class "Default")
      (node (ref "JP1") (pin "5") (pinfunction "5_5") (pintype "passive"))
      (node (ref "U1") (pin "1") (pinfunction "A1_1") (pintype "bidirectional"))
    )
    (net (code "34") (name "KICK") (class "Default")
      (node (ref "R19") (pin "1") (pinfunction "1_1") (pintype "passive"))
      (node (ref "U$2") (pin "23") (pinfunction "PB3_23") (pintype "bidirectional"))
    )
    (net (code "35") (name "LINE") (class "Default")
      (node (ref "D16") (pin "A") (pinfunction "A_A") (pintype "passive"))
      (node (ref "D17") (pin "A") (pinfunction "A_A") (pintype "passive"))
      (node (ref "R70") (pin "2") (pinfunction "2_2") (pintype "passive"))
    )
    (net (code "36") (name "MISO") (class "Default")
      (node (ref "U$2") (pin "8") (pinfunction "PB0_8") (pintype "bidirectional"))
      (node (ref "U1") (pin "17") (pinfunction "B3_17") (pintype "bidirectional"))
    )
    (net (code "37") (name "MISO_3V") (class "Default")
      (node (ref "JP1") (pin "3") (pinfunction "3_3") (pintype "passive"))
      (node (ref "U1") (pin "4") (pinfunction "A3_4") (pintype "bidirectional"))
    )
    (net (code "38") (name "MOSI") (class "Default")
      (node (ref "U$2") (pin "9") (pinfunction "PB1_9") (pintype "bidirectional"))
      (node (ref "U1") (pin "16") (pinfunction "B4_16") (pintype "bidirectional"))
    )
    (net (code "39") (name "MOSI_3V") (class "Default")
      (node (ref "JP1") (pin "2") (pinfunction "2_2") (pintype "passive"))
      (node (ref "U1") (pin "5") (pinfunction "A4_5") (pintype "bidirectional"))
    )
    (net (code "40") (name "NOTAUS") (class "Default")
      (node (ref "D16") (pin "C") (pinfunction "C_C") (pintype "passive"))
      (node (ref "R14") (pin "1") (pinfunction "1_1") (pintype "passive"))
      (node (ref "R55") (pin "2") (pinfunction "2_2") (pintype "passive"))
      (node (ref "U2") (pin "7") (pinfunction "1Y_7") (pintype "output"))
    )
    (net (code "41") (name "Net-(COIL_IN-P)") (class "Default")
      (node (ref "COIL_IN") (pin "P$1") (pinfunction "P_P$1") (pintype "passive"))
      (node (ref "Q2") (pin "D") (pinfunction "D_D") (pintype "passive"))
      (node (ref "R20") (pin "2") (pinfunction "2_2") (pintype "passive"))
      (node (ref "U$7") (pin "A") (pinfunction "A_A") (pintype "passive"))
    )
    (net (code "42") (name "Net-(D5-C)") (class "Default")
      (node (ref "D5") (pin "K") (pinfunction "C_K") (pintype "passive"))
      (node (ref "R18") (pin "1") (pinfunction "1_1") (pintype "passive"))
      (node (ref "U$6") (pin "6") (pinfunction "VO_6") (pintype "bidirectional"))
      (node (ref "U$6") (pin "7") (pinfunction "VO_7") (pintype "bidirectional"))
    )
    (net (code "43") (name "Net-(D5-PadA)") (class "Default")
      (node (ref "D5") (pin "A") (pinfunction "A_A") (pintype "passive"))
      (node (ref "R13") (pin "1") (pinfunction "1_1") (pintype "passive"))
    )
    (net (code "44") (name "Net-(D6-C)") (class "Default")
      (node (ref "C19") (pin "2") (pinfunction "2_2") (pintype "passive"))
      (node (ref "D6") (pin "K") (pinfunction "C_K") (pintype "passive"))
      (node (ref "L5") (pin "2") (pinfunction "2_2") (pintype "passive"))
      (node (ref "U3") (pin "8") (pinfunction "VSW_8") (pintype "output"))
    )
    (net (code "45") (name "Net-(D7-C)") (class "Default")
      (node (ref "C22") (pin "2") (pinfunction "2_2") (pintype "passive"))
      (node (ref "D7") (pin "K") (pinfunction "C_K") (pintype "passive"))
      (node (ref "L6") (pin "2") (pinfunction "2_2") (pintype "passive"))
      (node (ref "U4") (pin "8") (pinfunction "VSW_8") (pintype "output"))
    )
    (net (code "46") (name "Net-(D10-C)") (class "Default")
      (node (ref "D10") (pin "K") (pinfunction "C_K") (pintype "passive"))
      (node (ref "D8") (pin "A") (pinfunction "A_A") (pintype "passive"))
    )
    (net (code "47") (name "Net-(D11-C)") (class "Default")
      (node (ref "D11") (pin "K") (pinfunction "C_K") (pintype "passive"))
      (node (ref "D9") (pin "A") (pinfunction "A_A") (pintype "passive"))
    )
    (net (code "48") (name "Net-(D15-C)") (class "Default")
      (node (ref "D15") (pin "K") (pinfunction "C_K") (pintype "passive"))
      (node (ref "L1") (pin "2") (pinfunction "2_2") (pintype "passive"))
      (node (ref "U$8") (pin "2") (pinfunction "VOUT_2") (pintype "bidirectional"))
    )
    (net (code "49") (name "Net-(IC1A-+IN)") (class "Default")
      (node (ref "C15") (pin "1") (pinfunction "1_1") (pintype "passive"))
      (node (ref "C32") (pin "1") (pinfunction "1_1") (pintype "passive"))
      (node (ref "IC1") (pin "3") (pinfunction "+IN_3") (pintype "input"))
      (node (ref "IC1") (pin "5") (pinfunction "+IN_5") (pintype "input"))
      (node (ref "R101") (pin "1") (pinfunction "1_1") (pintype "passive"))
      (node (ref "R6") (pin "2") (pinfunction "2_2") (pintype "passive"))
    )
    (net (code "50") (name "Net-(IC1A--IN)") (class "Default")
      (node (ref "C14") (pin "1") (pinfunction "1_1") (pintype "passive"))
      (node (ref "C51") (pin "1") (pinfunction "1_1") (pintype "passive"))
      (node (ref "IC1") (pin "2") (pinfunction "-IN_2") (pintype "input"))
      (node (ref "OK1") (pin "7") (pinfunction "EMIT_7") (pintype "passive"))
      (node (ref "R11") (pin "2") (pinfunction "2_2") (pintype "passive"))
    )
    (net (code "51") (name "Net-(IC1A-OUT)") (class "Default")
      (node (ref "IC1") (pin "1") (pinfunction "OUT_1") (pintype "output"))
      (node (ref "R105") (pin "1") (pinfunction "1_1") (pintype "passive"))
    )
    (net (code "52") (name "Net-(IC1B--IN)") (class "Default")
      (node (ref "C46") (pin "1") (pinfunction "1_1") (pintype "passive"))
      (node (ref "IC1") (pin "6") (pinfunction "-IN_6") (pintype "input"))
      (node (ref "R4") (pin "2") (pinfunction "2_2") (pintype "passive"))
      (node (ref "R7") (pin "1") (pinfunction "1_1") (pintype "passive"))
    )
    (net (code "53") (name "Net-(IC1B-OUT)") (class "Default")
      (node (ref "IC1") (pin "7") (pinfunction "OUT_7") (pintype "output"))
      (node (ref "R9") (pin "1") (pinfunction "1_1") (pintype "passive"))
    )
    (net (code "54") (name "Net-(IC2A-EN)") (class "Default")
      (node (ref "IC2") (pin "5") (pinfunction "EN_5") (pintype "input"))
      (node (ref "R58") (pin "1") (pinfunction "1_1") (pintype "passive"))
    )
    (net (code "55") (name "Net-(IC2A-Q2)") (class "Default")
      (node (ref "IC2") (pin "10") (pinfunction "Q2_10") (pintype "output"))
      (node (ref "U2") (pin "1") (pinfunction "1A_1") (pintype "input"))
    )
    (net (code "56") (name "Net-(IC2A-Q3)") (class "Default")
      (node (ref "IC2") (pin "1") (pinfunction "Q3_1") (pintype "output"))
      (node (ref "U2") (pin "2") (pinfunction "1B_2") (pintype "input"))
    )
    (net (code "57") (name "Net-(IC4A--IN)") (class "Default")
      (node (ref "C36") (pin "1") (pinfunction "1_1") (pintype "passive"))
      (node (ref "IC4") (pin "2") (pinfunction "-IN_2") (pintype "input"))
      (node (ref "R21") (pin "2") (pinfunction "2_2") (pintype "passive"))
      (node (ref "R5") (pin "1") (pinfunction "1_1") (pintype "passive"))
      (node (ref "R52") (pin "2") (pinfunction "2_2") (pintype "passive"))
    )
    (net (code "58") (name "Net-(IC4A-OUT)") (class "Default")
      (node (ref "IC4") (pin "1") (pinfunction "OUT_1") (pintype "output"))
      (node (ref "U2") (pin "6") (pinfunction "2B_6") (pintype "input"))
    )
    (net (code "59") (name "Net-(LED1-PadA)") (class "Default")
      (node (ref "LED1") (pin "A") (pinfunction "A_A") (pintype "passive"))
      (node (ref "R39") (pin "1") (pinfunction "1_1") (pintype "passive"))
    )
    (net (code "60") (name "Net-(LED2-PadA)") (class "Default")
      (node (ref "LED2") (pin "A") (pinfunction "A_A") (pintype "passive"))
      (node (ref "R40") (pin "1") (pinfunction "1_1") (pintype "passive"))
    )
    (net (code "61") (name "Net-(LED3-PadA)") (class "Default")
      (node (ref "LED3") (pin "A") (pinfunction "A_A") (pintype "passive"))
      (node (ref "R41") (pin "1") (pinfunction "1_1") (pintype "passive"))
    )
    (net (code "62") (name "Net-(LED4-PadA)") (class "Default")
      (node (ref "LED4") (pin "A") (pinfunction "A_A") (pintype "passive"))
      (node (ref "R42") (pin "1") (pinfunction "1_1") (pintype "passive"))
    )
    (net (code "63") (name "Net-(LED5-PadA)") (class "Default")
      (node (ref "LED5") (pin "A") (pinfunction "A_A") (pintype "passive"))
      (node (ref "R43") (pin "1") (pinfunction "1_1") (pintype "passive"))
    )
    (net (code "64") (name "Net-(LED6-PadA)") (class "Default")
      (node (ref "LED6") (pin "A") (pinfunction "A_A") (pintype "passive"))
      (node (ref "R44") (pin "1") (pinfunction "1_1") (pintype "passive"))
    )
    (net (code "65") (name "Net-(LED7-PadA)") (class "Default")
      (node (ref "LED7") (pin "A") (pinfunction "A_A") (pintype "passive"))
      (node (ref "R45") (pin "1") (pinfunction "1_1") (pintype "passive"))
    )
    (net (code "66") (name "Net-(LED8-PadA)") (class "Default")
      (node (ref "LED8") (pin "A") (pinfunction "A_A") (pintype "passive"))
      (node (ref "R46") (pin "1") (pinfunction "1_1") (pintype "passive"))
    )
    (net (code "67") (name "Net-(LED9-PadA)") (class "Default")
      (node (ref "LED9") (pin "A") (pinfunction "A_A") (pintype "passive"))
      (node (ref "R49") (pin "1") (pinfunction "1_1") (pintype "passive"))
    )
    (net (code "68") (name "Net-(LED10-PadA)") (class "Default")
      (node (ref "LED10") (pin "A") (pinfunction "A_A") (pintype "passive"))
      (node (ref "R59") (pin "1") (pinfunction "1_1") (pintype "passive"))
    )
    (net (code "69") (name "Net-(OK1A-A)") (class "Default")
      (node (ref "OK1") (pin "1") (pinfunction "A_1") (pintype "passive"))
      (node (ref "R105") (pin "2") (pinfunction "2_2") (pintype "passive"))
    )
    (net (code "70") (name "Net-(OK1A-C)") (class "Default")
      (node (ref "OK1") (pin "2") (pinfunction "C_2") (pintype "passive"))
      (node (ref "OK1") (pin "3") (pinfunction "A_3") (pintype "passive"))
    )
    (net (code "71") (name "Net-(OK2A-A)") (class "Default")
      (node (ref "OK2") (pin "1") (pinfunction "A_1") (pintype "passive"))
      (node (ref "R9") (pin "2") (pinfunction "2_2") (pintype "passive"))
    )
    (net (code "72") (name "Net-(Q2-PadG)") (class "Default")
      (node (ref "Q2") (pin "G") (pinfunction "G_G") (pintype "passive"))
      (node (ref "R13") (pin "2") (pinfunction "2_2") (pintype "passive"))
      (node (ref "R18") (pin "2") (pinfunction "2_2") (pintype "passive"))
    )
    (net (code "73") (name "Net-(Q5-G)") (class "Default")
      (node (ref "D13") (pin "C") (pinfunction "C_C") (pintype "passive"))
      (node (ref "Q5") (pin "1") (pinfunction "G_1") (pintype "passive"))
      (node (ref "R200") (pin "1") (pinfunction "1_1") (pintype "passive"))
    )
    (net (code "74") (name "Net-(Q6-PadD)") (class "Default")
      (node (ref "Q6") (pin "D") (pinfunction "D_D") (pintype "passive"))
      (node (ref "R3") (pin "2") (pinfunction "2_2") (pintype "passive"))
    )
    (net (code "75") (name "Net-(Q6-PadG)") (class "Default")
      (node (ref "Q6") (pin "G") (pinfunction "G_G") (pintype "passive"))
      (node (ref "R12") (pin "2") (pinfunction "2_2") (pintype "passive"))
      (node (ref "T6") (pin "C") (pinfunction "C_C") (pintype "passive"))
    )
    (net (code "76") (name "Net-(R2-Pad2)") (class "Default")
      (node (ref "R2") (pin "2") (pinfunction "2_2") (pintype "passive"))
      (node (ref "R3") (pin "1") (pinfunction "1_1") (pintype "passive"))
    )
    (net (code "77") (name "Net-(R15-Pad1)") (class "Default")
      (node (ref "R15") (pin "1") (pinfunction "1_1") (pintype "passive"))
      (node (ref "U$5") (pin "6") (pinfunction "VO_6") (pintype "bidirectional"))
      (node (ref "U$5") (pin "7") (pinfunction "VO_7") (pintype "bidirectional"))
    )
    (net (code "78") (name "Net-(R15-Pad2)") (class "Default")
      (node (ref "R15") (pin "2") (pinfunction "2_2") (pintype "passive"))
      (node (ref "T6") (pin "B") (pinfunction "B_B") (pintype "passive"))
    )
    (net (code "79") (name "Net-(R32-Pad1)") (class "Default")
      (node (ref "R32") (pin "1") (pinfunction "1_1") (pintype "passive"))
      (node (ref "SJ1") (pin "1") (pinfunction "1_1") (pintype "passive"))
    )
    (net (code "80") (name "Net-(T2-B)") (class "Default")
      (node (ref "R19") (pin "2") (pinfunction "2_2") (pintype "passive"))
      (node (ref "R51") (pin "2") (pinfunction "2_2") (pintype "passive"))
      (node (ref "T2") (pin "1") (pinfunction "B_1") (pintype "passive"))
    )
    (net (code "81") (name "Net-(T2-C)") (class "Default")
      (node (ref "D17") (pin "C") (pinfunction "C_C") (pintype "passive"))
      (node (ref "T2") (pin "3") (pinfunction "C_3") (pintype "passive"))
      (node (ref "U$6") (pin "3") (pinfunction "CATHODE_3") (pintype "bidirectional"))
    )
    (net (code "82") (name "Net-(T3-B)") (class "Default")
      (node (ref "R24") (pin "2") (pinfunction "2_2") (pintype "passive"))
      (node (ref "T3") (pin "1") (pinfunction "B_1") (pintype "passive"))
    )
    (net (code "83") (name "Net-(T3-C)") (class "Default")
      (node (ref "D13") (pin "A") (pinfunction "A_A") (pintype "passive"))
      (node (ref "T3") (pin "3") (pinfunction "C_3") (pintype "passive"))
    )
    (net (code "84") (name "Net-(T4-B)") (class "Default")
      (node (ref "R25") (pin "2") (pinfunction "2_2") (pintype "passive"))
      (node (ref "T4") (pin "1") (pinfunction "B_1") (pintype "passive"))
    )
    (net (code "85") (name "Net-(T4-C)") (class "Default")
      (node (ref "R26") (pin "1") (pinfunction "1_1") (pintype "passive"))
      (node (ref "T4") (pin "3") (pinfunction "C_3") (pintype "passive"))
      (node (ref "U2") (pin "5") (pinfunction "2A_5") (pintype "input"))
    )
    (net (code "86") (name "Net-(T5-D)") (class "Default")
      (node (ref "JP3") (pin "3") (pinfunction "3_3") (pintype "passive"))
      (node (ref "T5") (pin "1") (pinfunction "D_1") (pintype "passive"))
    )
    (net (code "87") (name "Net-(T5-G)") (class "Default")
      (node (ref "R16") (pin "2") (pinfunction "2_2") (pintype "passive"))
      (node (ref "R47") (pin "2") (pinfunction "2_2") (pintype "passive"))
      (node (ref "T5") (pin "3") (pinfunction "G_3") (pintype "passive"))
    )
    (net (code "88") (name "Net-(U$1-RS)") (class "Default")
      (node (ref "R1") (pin "2") (pinfunction "2_2") (pintype "passive"))
      (node (ref "U$1") (pin "8") (pinfunction "RS_8") (pintype "input"))
    )
    (net (code "89") (name "Net-(U$2-AREF)") (class "Default")
      (node (ref "C6") (pin "2") (pinfunction "2_2") (pintype "passive"))
      (node (ref "U$2") (pin "21") (pinfunction "AREF_21") (pintype "bidirectional"))
    )
    (net (code "90") (name "Net-(U$2-PC4)") (class "Default")
      (node (ref "R57") (pin "1") (pinfunction "1_1") (pintype "passive"))
      (node (ref "U$2") (pin "17") (pinfunction "PC4_17") (pintype "bidirectional"))
    )
    (net (code "91") (name "Net-(U$2-PC6)") (class "Default")
      (node (ref "R55") (pin "1") (pinfunction "1_1") (pintype "passive"))
      (node (ref "U$2") (pin "22") (pinfunction "PC6_22") (pintype "bidirectional"))
    )
    (net (code "92") (name "Net-(U$2-PE1(XTAL1))") (class "Default")
      (node (ref "C5") (pin "2") (pinfunction "2_2") (pintype "passive"))
      (node (ref "Q1") (pin "1") (pinfunction "1_1") (pintype "passive"))
      (node (ref "U$2") (pin "10") (pinfunction "PE1(XTAL1)_10") (pintype "bidirectional"))
    )
    (net (code "93") (name "Net-(U$2-PE2(XTAL2))") (class "Default")
      (node (ref "C4") (pin "2") (pinfunction "2_2") (pintype "passive"))
      (node (ref "Q1") (pin "2") (pinfunction "2_2") (pintype "passive"))
      (node (ref "U$2") (pin "11") (pinfunction "PE2(XTAL2)_11") (pintype "bidirectional"))
    )
    (net (code "94") (name "Net-(U$5-ANODE)") (class "Default")
      (node (ref "R14") (pin "2") (pinfunction "2_2") (pintype "passive"))
      (node (ref "U$5") (pin "2") (pinfunction "ANODE_2") (pintype "bidirectional"))
    )
    (net (code "95") (name "Net-(U$6-ANODE)") (class "Default")
      (node (ref "R17") (pin "1") (pinfunction "1_1") (pintype "passive"))
      (node (ref "U$6") (pin "2") (pinfunction "ANODE_2") (pintype "bidirectional"))
    )
    (net (code "96") (name "Net-(U3-CB)") (class "Default")
      (node (ref "C19") (pin "1") (pinfunction "1_1") (pintype "passive"))
      (node (ref "U3") (pin "1") (pinfunction "CB_1") (pintype "input"))
    )
    (net (code "97") (name "Net-(U4-CB)") (class "Default")
      (node (ref "C22") (pin "1") (pinfunction "1_1") (pintype "passive"))
      (node (ref "U4") (pin "1") (pinfunction "CB_1") (pintype "input"))
    )
    (net (code "98") (name "Net-(VR1-C)") (class "Default")
      (node (ref "LED1") (pin "C") (pinfunction "C_C") (pintype "passive"))
      (node (ref "VR1") (pin "1") (pinfunction "C_1") (pintype "passive"))
    )
    (net (code "99") (name "Net-(VR1-R)") (class "Default")
      (node (ref "R33") (pin "1") (pinfunction "1_1") (pintype "passive"))
      (node (ref "R36") (pin "2") (pinfunction "2_2") (pintype "passive"))
      (node (ref "VR1") (pin "2") (pinfunction "R_2") (pintype "passive"))
    )
    (net (code "100") (name "Net-(VR2-C)") (class "Default")
      (node (ref "LED2") (pin "C") (pinfunction "C_C") (pintype "passive"))
      (node (ref "VR2") (pin "1") (pinfunction "C_1") (pintype "passive"))
    )
    (net (code "101") (name "Net-(VR2-R)") (class "Default")
      (node (ref "R34") (pin "1") (pinfunction "1_1") (pintype "passive"))
      (node (ref "R37") (pin "2") (pinfunction "2_2") (pintype "passive"))
      (node (ref "VR2") (pin "2") (pinfunction "R_2") (pintype "passive"))
    )
    (net (code "102") (name "Net-(VR3-C)") (class "Default")
      (node (ref "LED3") (pin "C") (pinfunction "C_C") (pintype "passive"))
      (node (ref "VR3") (pin "1") (pinfunction "C_1") (pintype "passive"))
    )
    (net (code "103") (name "Net-(VR3-R)") (class "Default")
      (node (ref "R35") (pin "1") (pinfunction "1_1") (pintype "passive"))
      (node (ref "R38") (pin "2") (pinfunction "2_2") (pintype "passive"))
      (node (ref "VR3") (pin "2") (pinfunction "R_2") (pintype "passive"))
    )
    (net (code "104") (name "Net-(X1A-KL)") (class "Default")
      (node (ref "F1") (pin "2") (pinfunction "2_2") (pintype "passive"))
      (node (ref "R59") (pin "2") (pinfunction "2_2") (pintype "passive"))
      (node (ref "X1") (pin "1") (pinfunction "KL_1") (pintype "passive"))
    )
    (net (code "105") (name "OC0A{slash}MOSI_A") (class "Default")
      (node (ref "JP4") (pin "1") (pinfunction "1_1") (pintype "passive"))
      (node (ref "SV1") (pin "1") (pinfunction "1_1") (pintype "passive"))
      (node (ref "U$2") (pin "2") (pinfunction "(MOSI_A/TXD)PD3_2") (pintype "bidirectional"))
    )
    (net (code "106") (name "OC1A_FREQ{slash}MISO_A") (class "Default")
      (node (ref "SV1") (pin "9") (pinfunction "9_9") (pintype "passive"))
      (node (ref "U$2") (pin "1") (pinfunction "(MISO_A)PD2_1") (pintype "bidirectional"))
    )
    (net (code "107") (name "RESET_NOTAUS") (class "Default")
      (node (ref "IC2") (pin "11") (pinfunction "R2_11") (pintype "input"))
      (node (ref "IC2") (pin "15") (pinfunction "R3_15") (pintype "input"))
      (node (ref "U$2") (pin "24") (pinfunction "PB4_24") (pintype "bidirectional"))
    )
    (net (code "108") (name "RST") (class "Default")
      (node (ref "SV1") (pin "5") (pinfunction "5_5") (pintype "passive"))
      (node (ref "U$2") (pin "31") (pinfunction "PE0(RESET)_31") (pintype "input"))
    )
    (net (code "109") (name "RST_ETH") (class "Default")
      (node (ref "U$2") (pin "32") (pinfunction "PD1_32") (pintype "bidirectional"))
      (node (ref "U1") (pin "14") (pinfunction "B6_14") (pintype "bidirectional"))
    )
    (net (code "110") (name "RST_ETH_3V") (class "Default")
      (node (ref "JP2") (pin "3") (pinfunction "3_3") (pintype "passive"))
      (node (ref "U1") (pin "7") (pinfunction "A6_7") (pintype "bidirectional"))
    )
    (net (code "111") (name "SCK") (class "Default")
      (node (ref "U$2") (pin "28") (pinfunction "(SCK)PB7_28") (pintype "bidirectional"))
      (node (ref "U1") (pin "15") (pinfunction "B5_15") (pintype "bidirectional"))
    )
    (net (code "112") (name "SCK_3V") (class "Default")
      (node (ref "JP1") (pin "1") (pinfunction "1_1") (pintype "passive"))
      (node (ref "U1") (pin "6") (pinfunction "A5_6") (pintype "bidirectional"))
    )
    (net (code "113") (name "SERVO_PWM") (class "Default")
      (node (ref "JP3") (pin "1") (pinfunction "1_1") (pintype "passive"))
      (node (ref "U$2") (pin "3") (pinfunction "PC1_3") (pintype "bidirectional"))
    )
    (net (code "114") (name "STBY") (class "Default")
      (node (ref "R57") (pin "2") (pinfunction "2_2") (pintype "passive"))
      (node (ref "U2") (pin "3") (pinfunction "2Y_3") (pintype "output"))
    )
    (net (code "115") (name "TASTER") (class "Default")
      (node (ref "C33") (pin "1") (pinfunction "1_1") (pintype "passive"))
      (node (ref "IC2") (pin "14") (pinfunction "S3_14") (pintype "input"))
      (node (ref "R22") (pin "2") (pinfunction "2_2") (pintype "passive"))
      (node (ref "S1") (pin "3") (pinfunction "P_3") (pintype "passive"))
      (node (ref "S1") (pin "4") (pinfunction "P1_4") (pintype "passive"))
    )
    (net (code "116") (name "WOL_ETH") (class "Default")
      (node (ref "U1") (pin "18") (pinfunction "B2_18") (pintype "bidirectional"))
    )
    (net (code "117") (name "WOL_ETH_3V") (class "Default")
      (node (ref "JP1") (pin "4") (pinfunction "4_4") (pintype "passive"))
      (node (ref "U1") (pin "3") (pinfunction "A2_3") (pintype "bidirectional"))
    )
    (net (code "118") (name "unconnected-(IC2A-Q0-Pad2)") (class "Default")
      (node (ref "IC2") (pin "2") (pinfunction "Q0_2") (pintype "output"))
    )
    (net (code "119") (name "unconnected-(IC2A-Q1-Pad9)") (class "Default")
      (node (ref "IC2") (pin "9") (pinfunction "Q1_9") (pintype "output"))
    )
    (net (code "120") (name "unconnected-(IC4B-OUT-Pad7)") (class "Default")
      (node (ref "IC4") (pin "7") (pinfunction "OUT_7") (pintype "output"))
    )
    (net (code "121") (name "unconnected-(OK2B-A-Pad3)") (class "Default")
      (node (ref "OK2") (pin "3") (pinfunction "A_3") (pintype "passive"))
    )
    (net (code "122") (name "unconnected-(OK2B-C-Pad4)") (class "Default")
      (node (ref "OK2") (pin "4") (pinfunction "C_4") (pintype "passive"))
    )
    (net (code "123") (name "unconnected-(OK2B-COL-Pad6)") (class "Default")
      (node (ref "OK2") (pin "6") (pinfunction "COL_6") (pintype "passive"))
    )
    (net (code "124") (name "unconnected-(OK2B-EMIT-Pad5)") (class "Default")
      (node (ref "OK2") (pin "5") (pinfunction "EMIT_5") (pintype "passive"))
    )
    (net (code "125") (name "unconnected-(Q3-PadG)") (class "Default")
      (node (ref "Q3") (pin "G") (pinfunction "G_G") (pintype "passive"))
    )
    (net (code "126") (name "unconnected-(Q3-PadS)") (class "Default")
      (node (ref "Q3") (pin "S") (pinfunction "S_S") (pintype "passive"))
    )
    (net (code "127") (name "unconnected-(RJ_1-PadP$1)") (class "Default")
      (node (ref "RJ_1") (pin "P$1") (pinfunction "P$1_P$1") (pintype "bidirectional"))
    )
    (net (code "128") (name "unconnected-(RJ_2-PadP$1)") (class "Default")
      (node (ref "RJ_2") (pin "P$1") (pinfunction "P$1_P$1") (pintype "bidirectional"))
    )
    (net (code "129") (name "unconnected-(SV1-Pad3)") (class "Default")
      (node (ref "SV1") (pin "3") (pinfunction "3_3") (pintype "passive"))
    )
    (net (code "130") (name "unconnected-(U$1-VREF-Pad5)") (class "Default")
      (node (ref "U$1") (pin "5") (pinfunction "VREF_5") (pintype "output"))
    )
    (net (code "131") (name "unconnected-(U$4-0V-Pad5)") (class "Default")
      (node (ref "U$4") (pin "5") (pinfunction "0V_5") (pintype "bidirectional"))
    )
    (net (code "132") (name "unconnected-(U$9-S1-Pad6)") (class "Default")
      (node (ref "U$9") (pin "6") (pinfunction "S1_6") (pintype "passive"))
    )
    (net (code "133") (name "unconnected-(U$9-S2-Pad7)") (class "Default")
      (node (ref "U$9") (pin "7") (pinfunction "S2_7") (pintype "passive"))
    )
    (net (code "134") (name "unconnected-(U$9-W11-Pad1)") (class "Default")
      (node (ref "U$9") (pin "1") (pinfunction "W11_1") (pintype "passive"))
    )
    (net (code "135") (name "unconnected-(U$9-W12-Pad9)") (class "Default")
      (node (ref "U$9") (pin "9") (pinfunction "W12_9") (pintype "passive"))
    )
    (net (code "136") (name "unconnected-(U$9-W21-Pad2)") (class "Default")
      (node (ref "U$9") (pin "2") (pinfunction "W21_2") (pintype "passive"))
    )
    (net (code "137") (name "unconnected-(U$9-W22-Pad10)") (class "Default")
      (node (ref "U$9") (pin "10") (pinfunction "W22_10") (pintype "passive"))
    )
    (net (code "138") (name "unconnected-(U$9-W31-Pad3)") (class "Default")
      (node (ref "U$9") (pin "3") (pinfunction "W31_3") (pintype "passive"))
    )
    (net (code "139") (name "unconnected-(U$9-W32-Pad11)") (class "Default")
      (node (ref "U$9") (pin "11") (pinfunction "W32_11") (pintype "passive"))
    )
    (net (code "140") (name "unconnected-(U$9-W41-Pad4)") (class "Default")
      (node (ref "U$9") (pin "4") (pinfunction "W41_4") (pintype "passive"))
    )
    (net (code "141") (name "unconnected-(U$9-W42-Pad12)") (class "Default")
      (node (ref "U$9") (pin "12") (pinfunction "W42_12") (pintype "passive"))
    )
    (net (code "142") (name "unconnected-(U3-NC-Pad3)") (class "Default")
      (node (ref "U3") (pin "3") (pinfunction "NC_3") (pintype "no_connect"))
    )
    (net (code "143") (name "unconnected-(U3-NC_2-Pad2)") (class "Default")
      (node (ref "U3") (pin "2") (pinfunction "NC_2_2") (pintype "no_connect"))
    )
    (net (code "144") (name "unconnected-(U3-ON{slash}~{OFF}-Pad5)") (class "Default")
      (node (ref "U3") (pin "5") (pinfunction "ON/~{OFF}_5") (pintype "input"))
    )
    (net (code "145") (name "unconnected-(U4-NC-Pad3)") (class "Default")
      (node (ref "U4") (pin "3") (pinfunction "NC_3") (pintype "no_connect"))
    )
    (net (code "146") (name "unconnected-(U4-NC_2-Pad2)") (class "Default")
      (node (ref "U4") (pin "2") (pinfunction "NC_2_2") (pintype "no_connect"))
    )
    (net (code "147") (name "unconnected-(U4-ON{slash}~{OFF}-Pad5)") (class "Default")
      (node (ref "U4") (pin "5") (pinfunction "ON/~{OFF}_5") (pintype "input"))
    )
    (net (code "148") (name "ÜBERSPANNUNG") (class "Default")
      (node (ref "C24") (pin "1") (pinfunction "1_1") (pintype "passive"))
      (node (ref "C41") (pin "1") (pinfunction "1_1") (pintype "passive"))
      (node (ref "IC2") (pin "12") (pinfunction "S2_12") (pintype "input"))
      (node (ref "OK2") (pin "7") (pinfunction "EMIT_7") (pintype "passive"))
      (node (ref "R10") (pin "2") (pinfunction "2_2") (pintype "passive"))
    )
  )
)
